# PM_Controller_v1p06.net
KiCad netlist of a schematic drawn in EAGLE
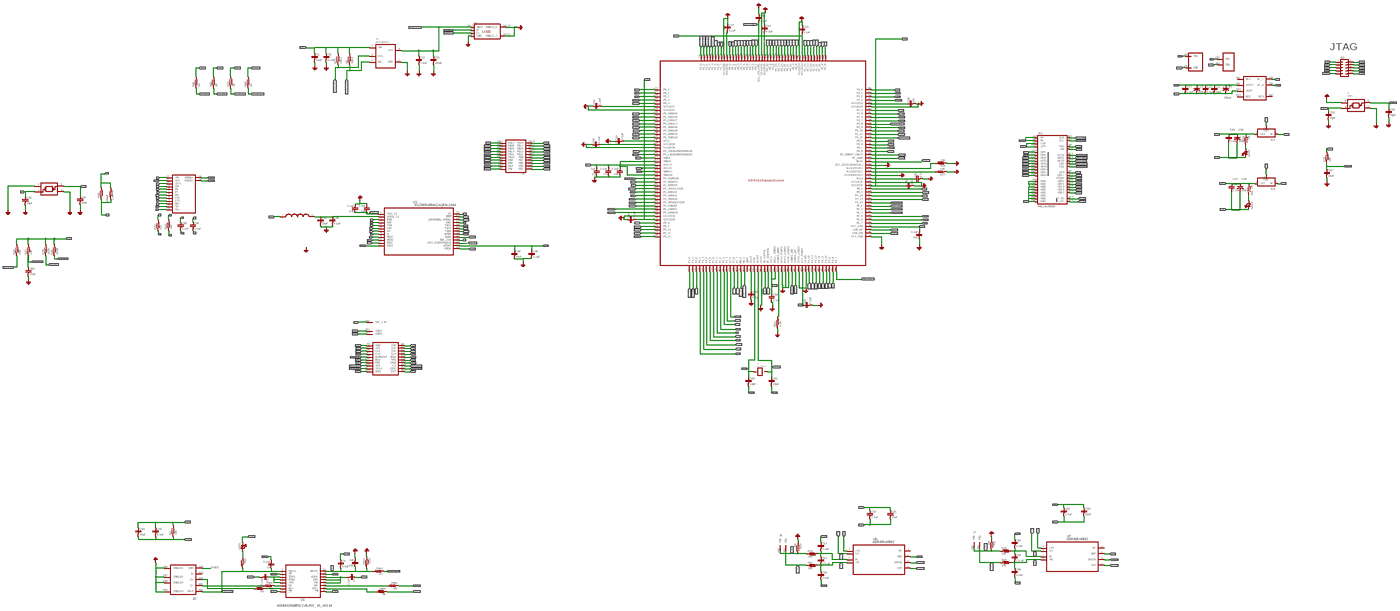
[diagram p0: schematic, sheet 1, overview]
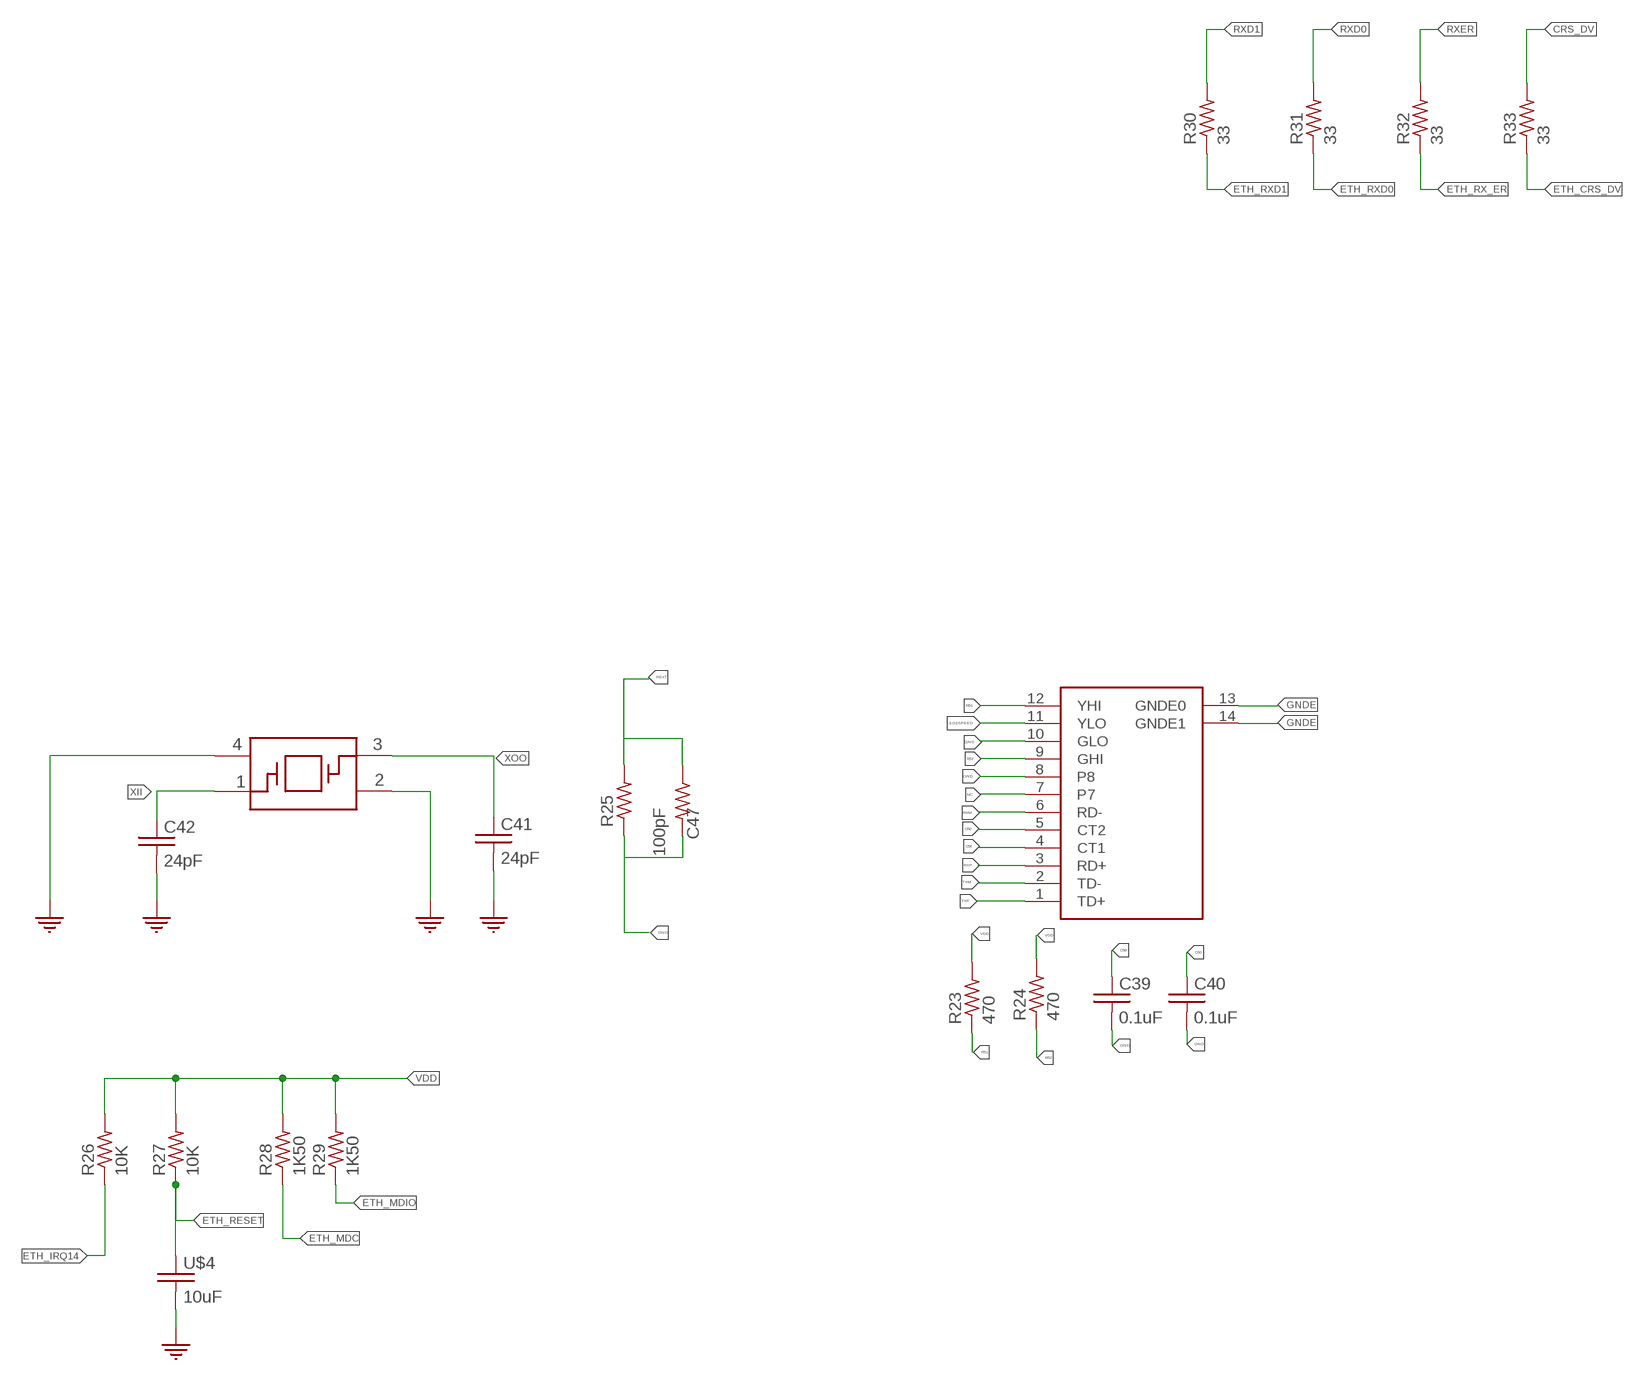
[diagram p1: schematic, sheet 1, part 1 of 7]
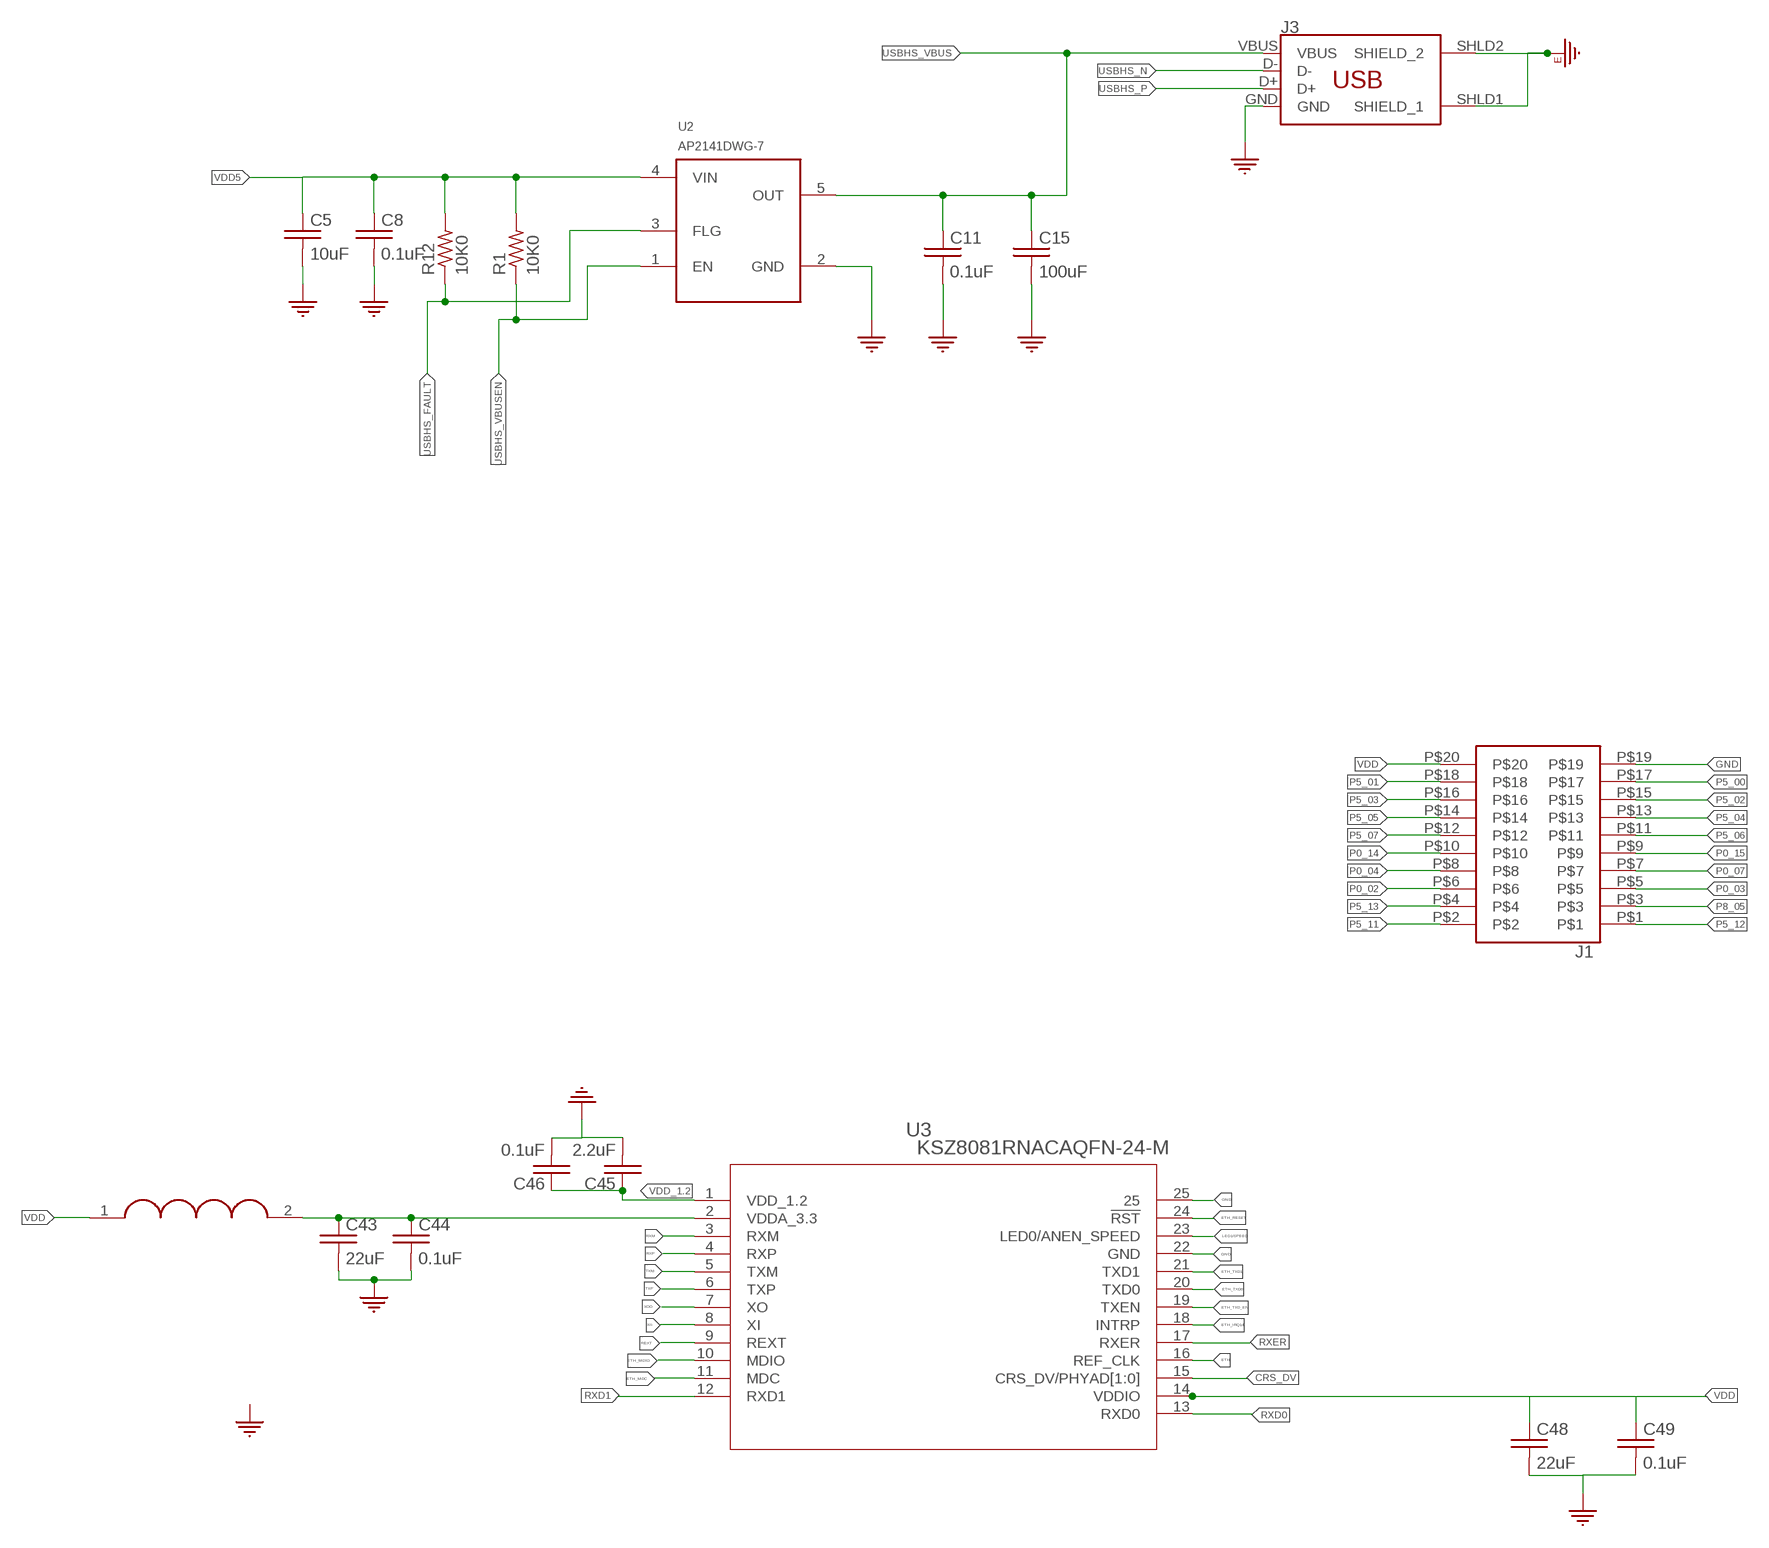
[diagram p2: schematic, sheet 1, part 2 of 7]
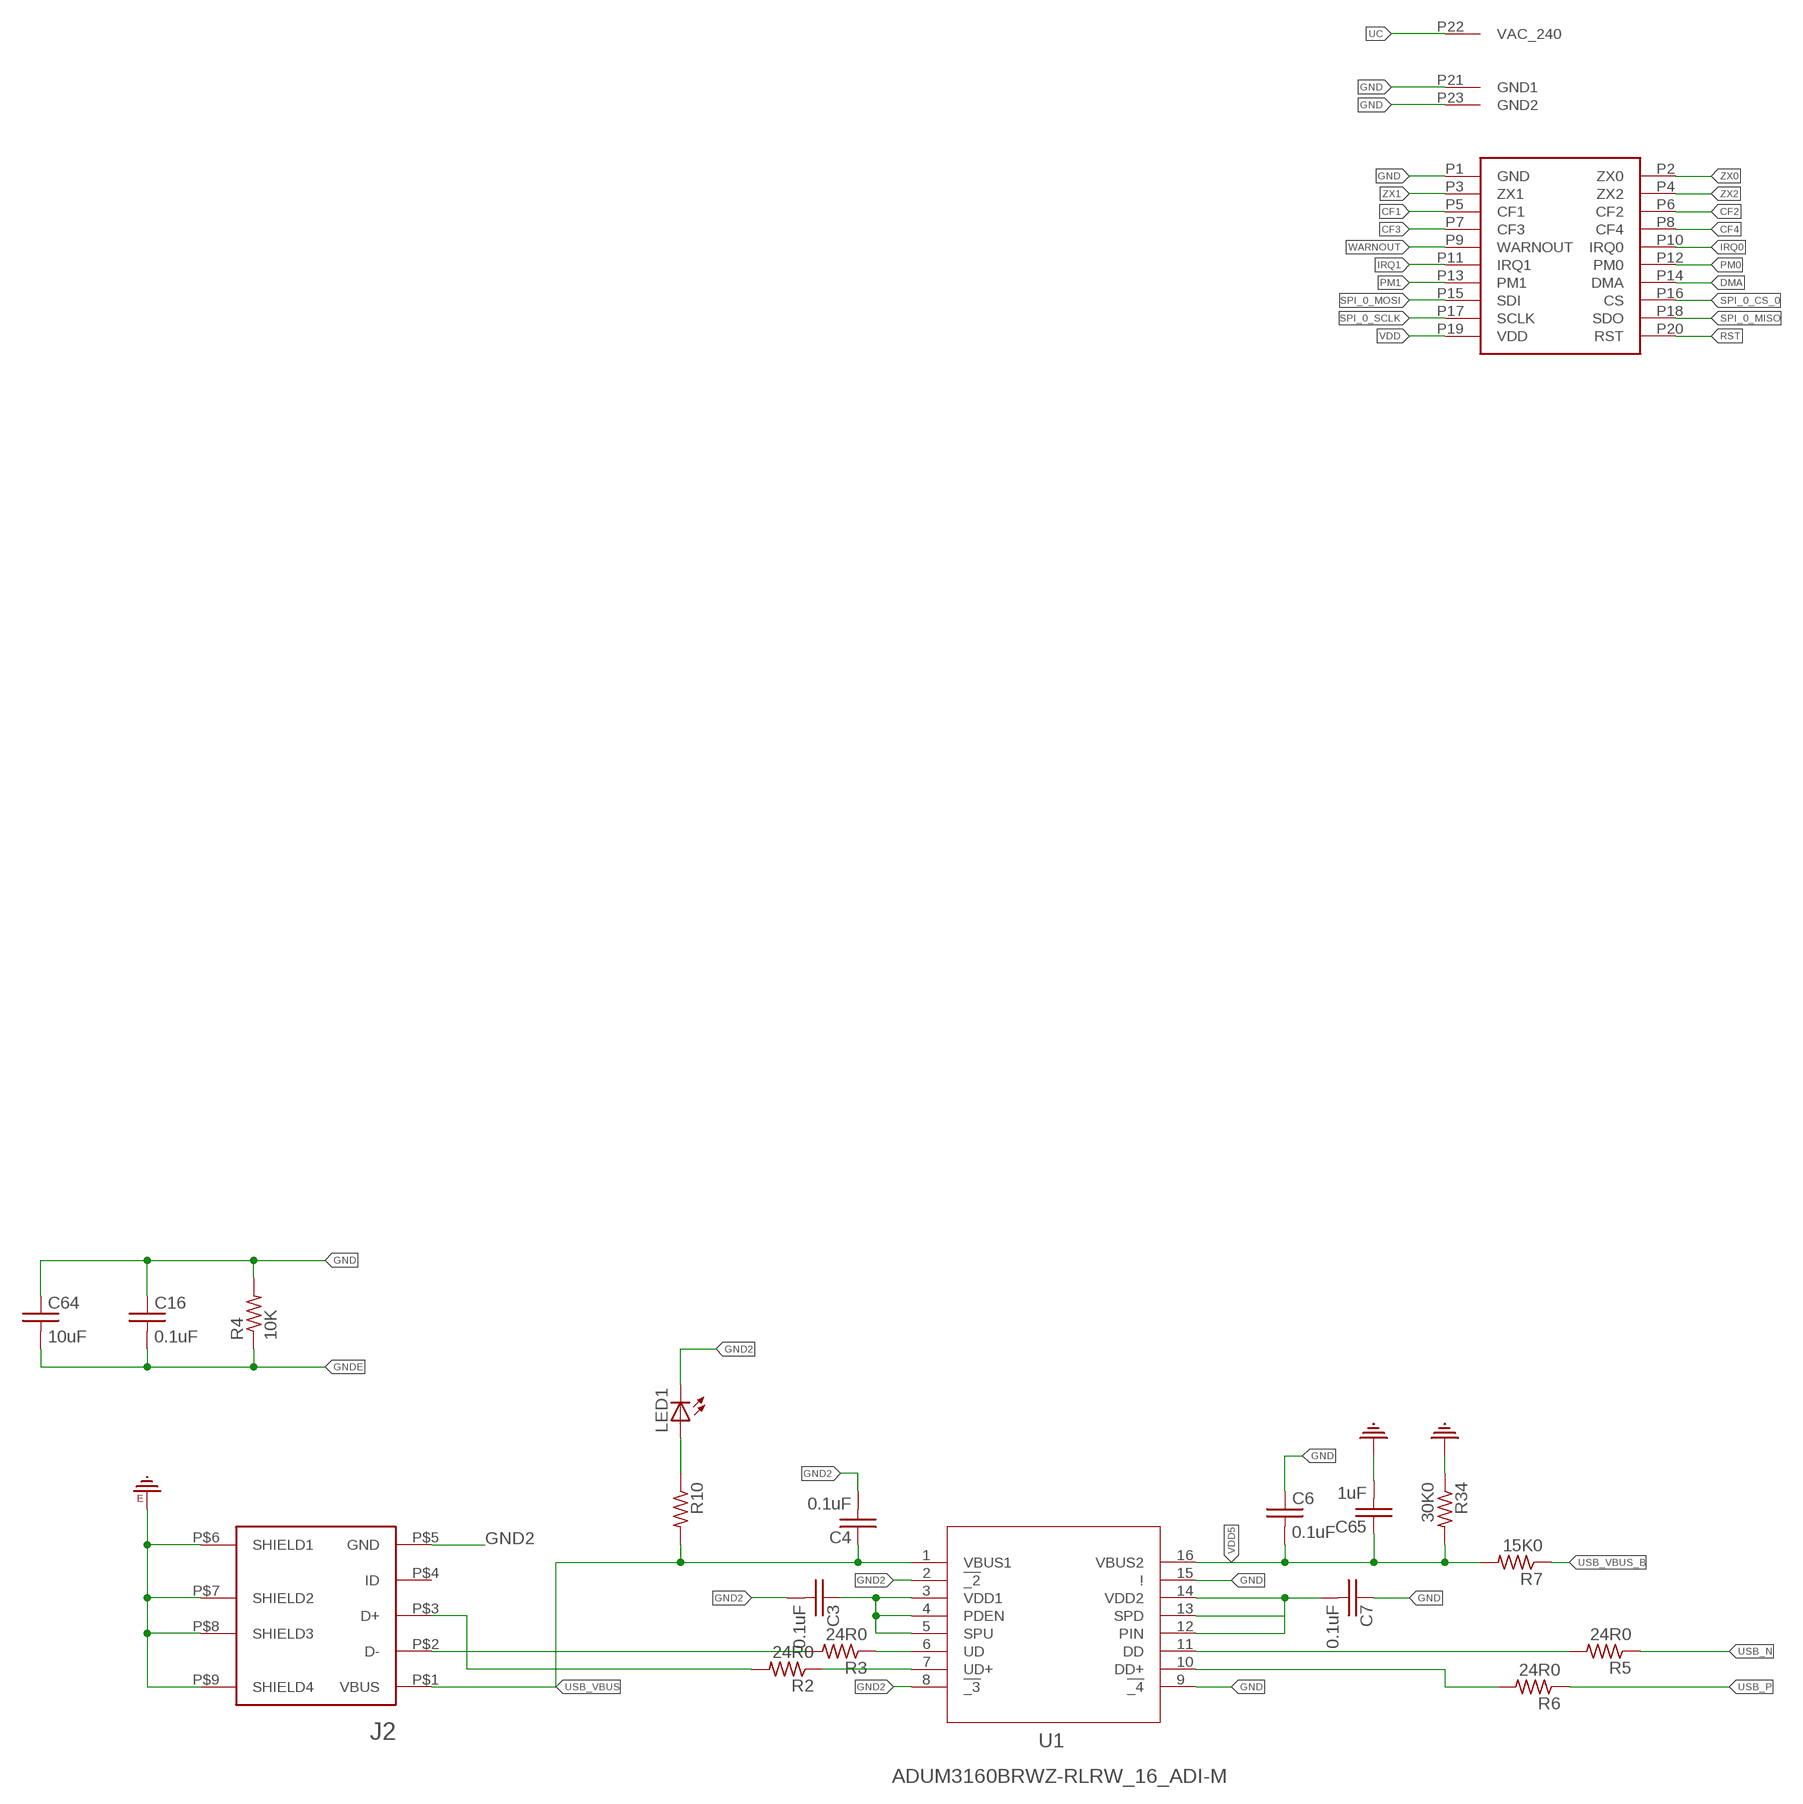
[diagram p3: schematic, sheet 1, part 3 of 7]
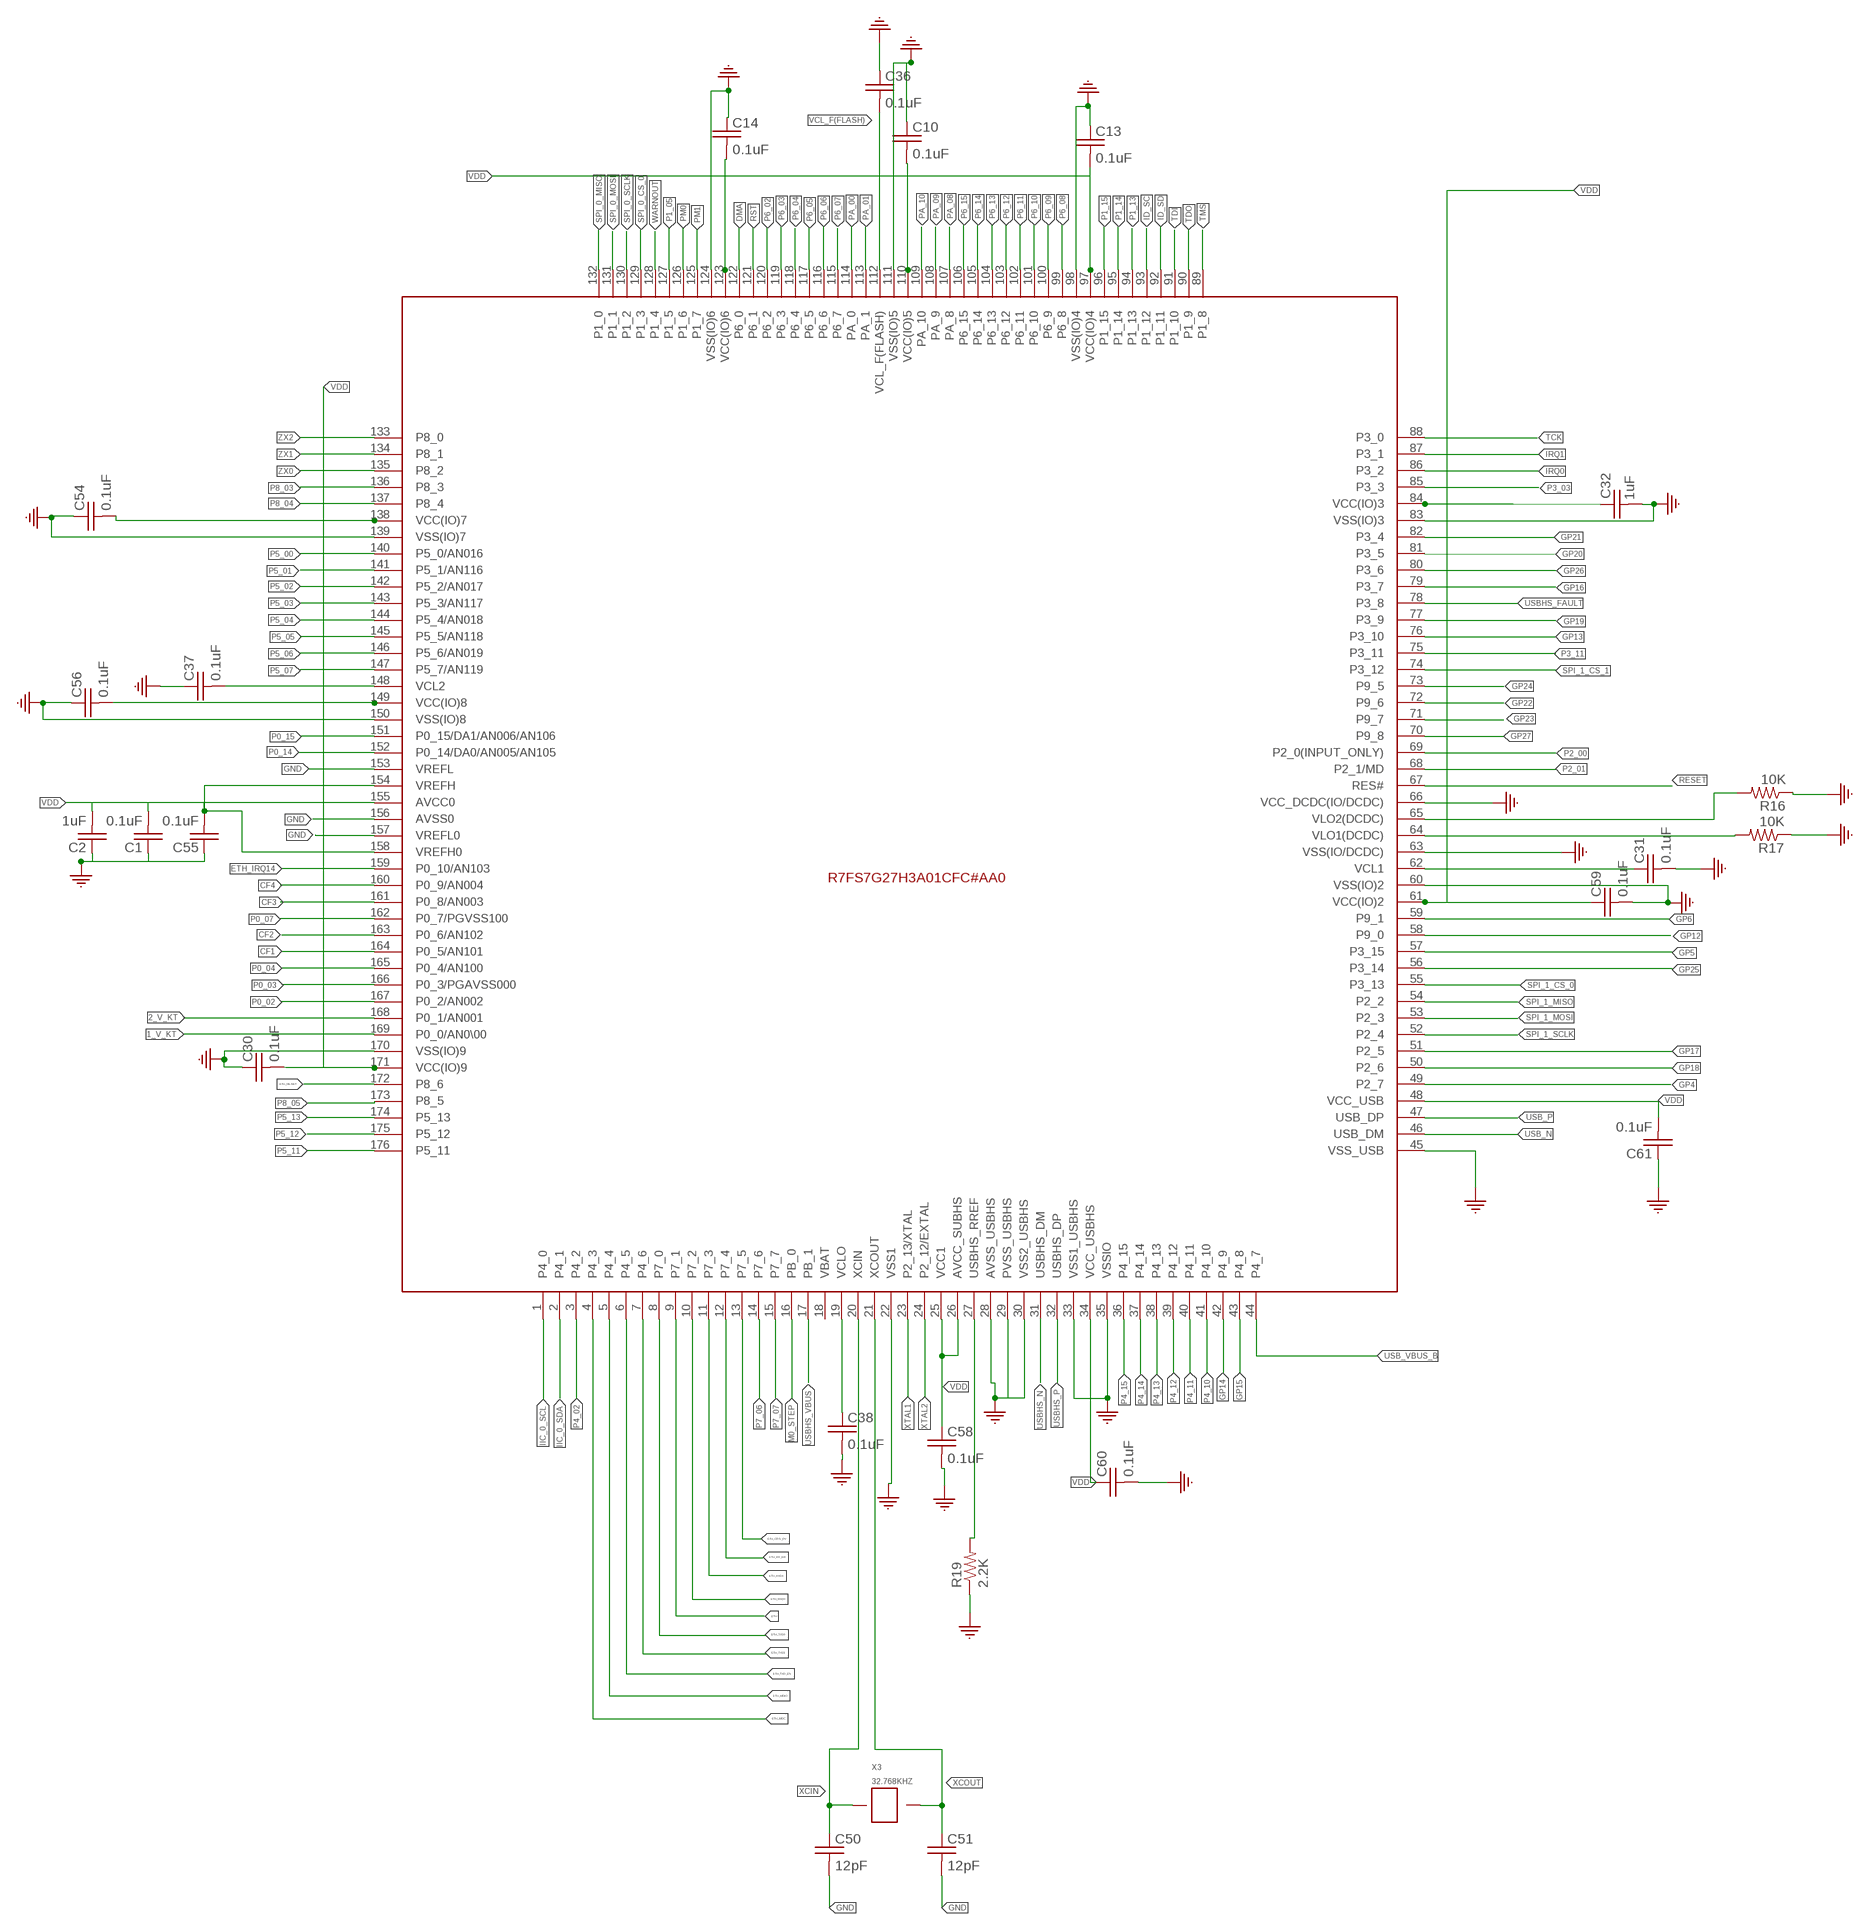
[diagram p4: schematic, sheet 1, part 4 of 7]
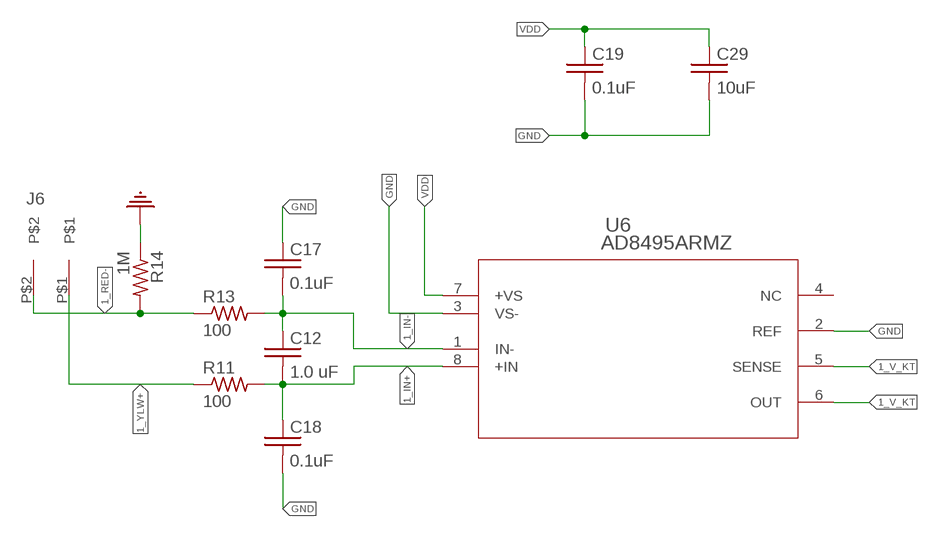
[diagram p5: schematic, sheet 1, part 5 of 7]
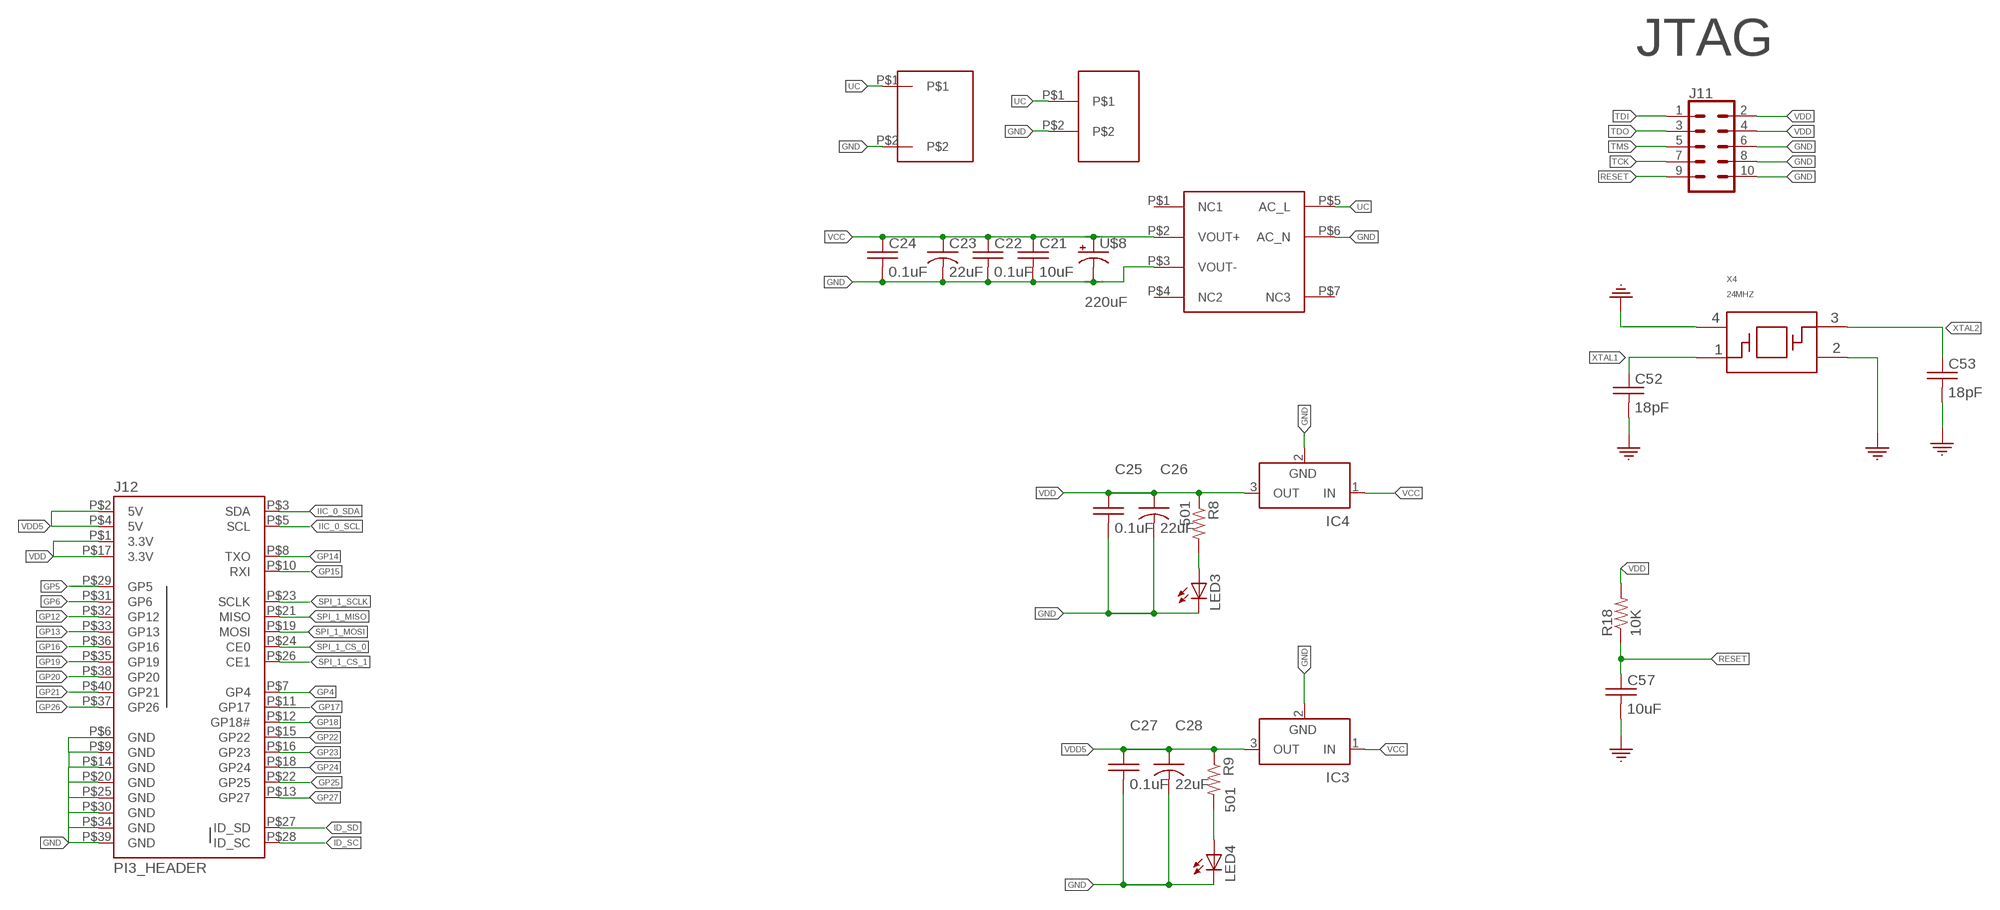
[diagram p6: schematic, sheet 1, part 6 of 7]
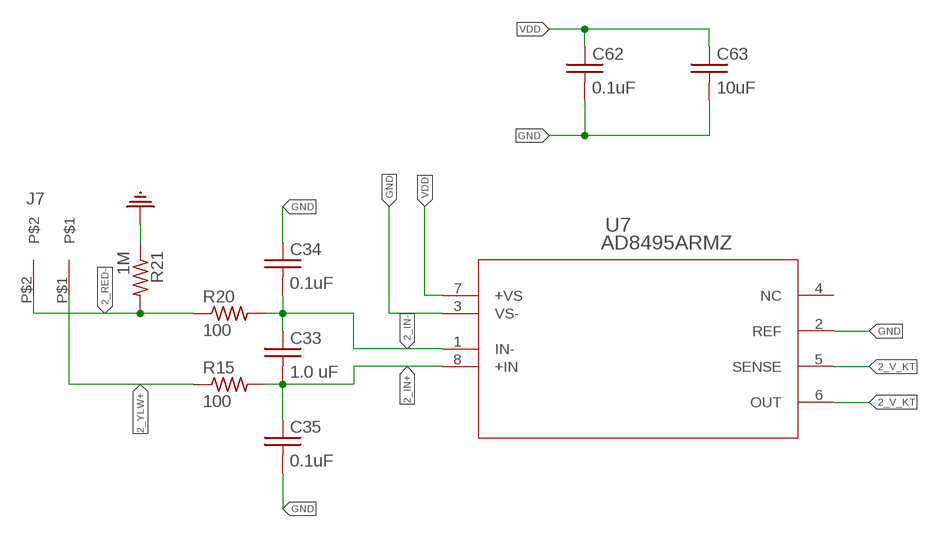
[diagram p7: schematic, sheet 1, part 7 of 7]

(export (version "E")
  (design (tool "Eeschema 10.0.6"))
  (components
    (comp (ref "C1")
      (value "0.1uF")
      (footprint "eagle-import:0402")
      (libsource (lib "eagle-import") (part "C_0402"))
    )
    (comp (ref "C2")
      (value "1uF")
      (footprint "eagle-import:0402")
      (libsource (lib "eagle-import") (part "C_0402"))
    )
    (comp (ref "C3")
      (value "0.1uF")
      (footprint "eagle-import:0402")
      (libsource (lib "eagle-import") (part "C_0402"))
    )
    (comp (ref "C4")
      (value "0.1uF")
      (footprint "eagle-import:0402")
      (libsource (lib "eagle-import") (part "C_0402"))
    )
    (comp (ref "C5")
      (value "10uF")
      (footprint "eagle-import:0402")
      (libsource (lib "eagle-import") (part "C_0402"))
    )
    (comp (ref "C6")
      (value "0.1uF")
      (footprint "eagle-import:0402")
      (libsource (lib "eagle-import") (part "C_0402"))
    )
    (comp (ref "C7")
      (value "0.1uF")
      (footprint "eagle-import:0402")
      (libsource (lib "eagle-import") (part "C_0402"))
    )
    (comp (ref "C8")
      (value "0.1uF")
      (footprint "eagle-import:0402")
      (libsource (lib "eagle-import") (part "C_0402"))
    )
    (comp (ref "C10")
      (value "0.1uF")
      (footprint "eagle-import:0402")
      (libsource (lib "eagle-import") (part "C_0402"))
    )
    (comp (ref "C11")
      (value "0.1uF")
      (footprint "eagle-import:0402")
      (libsource (lib "eagle-import") (part "C_0402"))
    )
    (comp (ref "C12")
      (value "1.0 uF")
      (footprint "eagle-import:0402")
      (libsource (lib "eagle-import") (part "C_0402"))
    )
    (comp (ref "C13")
      (value "0.1uF")
      (footprint "eagle-import:0402")
      (libsource (lib "eagle-import") (part "C_0402"))
    )
    (comp (ref "C14")
      (value "0.1uF")
      (footprint "eagle-import:0402")
      (libsource (lib "eagle-import") (part "C_0402"))
    )
    (comp (ref "C15")
      (value "100uF")
      (footprint "eagle-import:C1210")
      (libsource (lib "eagle-import") (part "C_1210"))
    )
    (comp (ref "C16")
      (value "0.1uF")
      (footprint "eagle-import:0402")
      (libsource (lib "eagle-import") (part "C_0402"))
    )
    (comp (ref "C17")
      (value "0.1uF")
      (footprint "eagle-import:0402")
      (libsource (lib "eagle-import") (part "C_0402"))
    )
    (comp (ref "C18")
      (value "0.1uF")
      (footprint "eagle-import:0402")
      (libsource (lib "eagle-import") (part "C_0402"))
    )
    (comp (ref "C19")
      (value "0.1uF")
      (footprint "eagle-import:0402")
      (libsource (lib "eagle-import") (part "C_0402"))
    )
    (comp (ref "C20")
      (value "CAP_THIN_FILM_TDK_32922CAP")
      (footprint "eagle-import:CAP_THIN_FILM_32922")
      (libsource (lib "eagle-import") (part "CAP_THIN_FILM_TDK_32922CAP"))
    )
    (comp (ref "C21")
      (value "10uF")
      (footprint "eagle-import:0402")
      (libsource (lib "eagle-import") (part "C_0402"))
    )
    (comp (ref "C22")
      (value "0.1uF")
      (footprint "eagle-import:0402")
      (libsource (lib "eagle-import") (part "C_0402"))
    )
    (comp (ref "C23")
      (value "22uF")
      (footprint "eagle-import:C1206")
      (libsource (lib "eagle-import") (part "C-USC1206"))
    )
    (comp (ref "C24")
      (value "0.1uF")
      (footprint "eagle-import:0402")
      (libsource (lib "eagle-import") (part "C_0402"))
    )
    (comp (ref "C25")
      (value "0.1uF")
      (footprint "eagle-import:0402")
      (libsource (lib "eagle-import") (part "C_0402"))
    )
    (comp (ref "C26")
      (value "22uF")
      (footprint "eagle-import:C1206")
      (libsource (lib "eagle-import") (part "C-USC1206"))
    )
    (comp (ref "C27")
      (value "0.1uF")
      (footprint "eagle-import:0402")
      (libsource (lib "eagle-import") (part "C_0402"))
    )
    (comp (ref "C28")
      (value "22uF")
      (footprint "eagle-import:C1206")
      (libsource (lib "eagle-import") (part "C-USC1206"))
    )
    (comp (ref "C29")
      (value "10uF")
      (footprint "eagle-import:0402")
      (libsource (lib "eagle-import") (part "C_0402"))
    )
    (comp (ref "C30")
      (value "0.1uF")
      (footprint "eagle-import:0402")
      (libsource (lib "eagle-import") (part "C_0402"))
    )
    (comp (ref "C31")
      (value "0.1uF")
      (footprint "eagle-import:0402")
      (libsource (lib "eagle-import") (part "C_0402"))
    )
    (comp (ref "C32")
      (value "1uF")
      (footprint "eagle-import:0402")
      (libsource (lib "eagle-import") (part "C_0402"))
    )
    (comp (ref "C33")
      (value "1.0 uF")
      (footprint "eagle-import:0402")
      (libsource (lib "eagle-import") (part "C_0402"))
    )
    (comp (ref "C34")
      (value "0.1uF")
      (footprint "eagle-import:0402")
      (libsource (lib "eagle-import") (part "C_0402"))
    )
    (comp (ref "C35")
      (value "0.1uF")
      (footprint "eagle-import:0402")
      (libsource (lib "eagle-import") (part "C_0402"))
    )
    (comp (ref "C36")
      (value "0.1uF")
      (footprint "eagle-import:0402")
      (libsource (lib "eagle-import") (part "C_0402"))
    )
    (comp (ref "C37")
      (value "0.1uF")
      (footprint "eagle-import:0402")
      (libsource (lib "eagle-import") (part "C_0402"))
    )
    (comp (ref "C38")
      (value "0.1uF")
      (footprint "eagle-import:0402")
      (libsource (lib "eagle-import") (part "C_0402"))
    )
    (comp (ref "C39")
      (value "0.1uF")
      (footprint "eagle-import:0402")
      (libsource (lib "eagle-import") (part "C_0402"))
    )
    (comp (ref "C40")
      (value "0.1uF")
      (footprint "eagle-import:0402")
      (libsource (lib "eagle-import") (part "C_0402"))
    )
    (comp (ref "C41")
      (value "24pF")
      (footprint "eagle-import:0402")
      (libsource (lib "eagle-import") (part "C_0402"))
    )
    (comp (ref "C42")
      (value "24pF")
      (footprint "eagle-import:0402")
      (libsource (lib "eagle-import") (part "C_0402"))
    )
    (comp (ref "C43")
      (value "22uF")
      (footprint "eagle-import:0603")
      (libsource (lib "eagle-import") (part "C_0603"))
    )
    (comp (ref "C44")
      (value "0.1uF")
      (footprint "eagle-import:0402")
      (libsource (lib "eagle-import") (part "C_0402"))
    )
    (comp (ref "C45")
      (value "2.2uF")
      (footprint "eagle-import:0402")
      (libsource (lib "eagle-import") (part "C_0402"))
    )
    (comp (ref "C46")
      (value "0.1uF")
      (footprint "eagle-import:0402")
      (libsource (lib "eagle-import") (part "C_0402"))
    )
    (comp (ref "C47")
      (value "100pF")
      (footprint "eagle-import:0402")
      (libsource (lib "eagle-import") (part "R_0402"))
    )
    (comp (ref "C48")
      (value "22uF")
      (footprint "eagle-import:0603")
      (libsource (lib "eagle-import") (part "C_0603"))
    )
    (comp (ref "C49")
      (value "0.1uF")
      (footprint "eagle-import:0402")
      (libsource (lib "eagle-import") (part "C_0402"))
    )
    (comp (ref "C50")
      (value "12pF")
      (footprint "eagle-import:0402")
      (libsource (lib "eagle-import") (part "C_0402"))
    )
    (comp (ref "C51")
      (value "12pF")
      (footprint "eagle-import:0402")
      (libsource (lib "eagle-import") (part "C_0402"))
    )
    (comp (ref "C52")
      (value "18pF")
      (footprint "eagle-import:0402")
      (libsource (lib "eagle-import") (part "C_0402"))
    )
    (comp (ref "C53")
      (value "18pF")
      (footprint "eagle-import:0402")
      (libsource (lib "eagle-import") (part "C_0402"))
    )
    (comp (ref "C54")
      (value "0.1uF")
      (footprint "eagle-import:0402")
      (libsource (lib "eagle-import") (part "C_0402"))
    )
    (comp (ref "C55")
      (value "0.1uF")
      (footprint "eagle-import:0402")
      (libsource (lib "eagle-import") (part "C_0402"))
    )
    (comp (ref "C56")
      (value "0.1uF")
      (footprint "eagle-import:0402")
      (libsource (lib "eagle-import") (part "C_0402"))
    )
    (comp (ref "C57")
      (value "10uF")
      (footprint "eagle-import:0402")
      (libsource (lib "eagle-import") (part "C_0402"))
    )
    (comp (ref "C58")
      (value "0.1uF")
      (footprint "eagle-import:0402")
      (libsource (lib "eagle-import") (part "C_0402"))
    )
    (comp (ref "C59")
      (value "0.1uF")
      (footprint "eagle-import:0402")
      (libsource (lib "eagle-import") (part "C_0402"))
    )
    (comp (ref "C60")
      (value "0.1uF")
      (footprint "eagle-import:0402")
      (libsource (lib "eagle-import") (part "C_0402"))
    )
    (comp (ref "C61")
      (value "0.1uF")
      (footprint "eagle-import:0402")
      (libsource (lib "eagle-import") (part "C_0402"))
    )
    (comp (ref "C62")
      (value "0.1uF")
      (footprint "eagle-import:0402")
      (libsource (lib "eagle-import") (part "C_0402"))
    )
    (comp (ref "C63")
      (value "10uF")
      (footprint "eagle-import:0402")
      (libsource (lib "eagle-import") (part "C_0402"))
    )
    (comp (ref "C64")
      (value "10uF")
      (footprint "eagle-import:0402")
      (libsource (lib "eagle-import") (part "C_0402"))
    )
    (comp (ref "C65")
      (value "1uF")
      (footprint "eagle-import:0402")
      (libsource (lib "eagle-import") (part "C_0402"))
    )
    (comp (ref "FB2/2")
      (value "FB_0805_120_OHM")
      (footprint "eagle-import:0805")
      (libsource (lib "eagle-import") (part "FB_0805_120_OHM"))
    )
    (comp (ref "IC3")
      (value "LT1129CST5")
      (footprint "eagle-import:SOT223")
      (fields (field (name "MPN") "LT1129CST-5#PBF"))
      (libsource (lib "eagle-import") (part "LT1129CST5"))
    )
    (comp (ref "IC4")
      (value "LT1129CST3")
      (footprint "eagle-import:SOT223")
      (fields (field (name "MPN") "LT1129CST-5#PBF"))
      (libsource (lib "eagle-import") (part "LT1129CST3"))
    )
    (comp (ref "J1")
      (value "2_X_10_HEADER_GENERIC")
      (footprint "eagle-import:2_X_10_.1_INCH")
      (libsource (lib "eagle-import") (part "2_X_10_HEADER_GENERIC"))
    )
    (comp (ref "J2")
      (value "USB_MICRO-B")
      (footprint "eagle-import:USB_MICRO-B")
      (libsource (lib "eagle-import") (part "USB_MICRO-B"))
    )
    (comp (ref "J3")
      (value "USB_A")
      (footprint "eagle-import:USB_A_SMT")
      (libsource (lib "eagle-import") (part "USB_A"))
    )
    (comp (ref "J4")
      (value "RJ45_WITH_ELEC")
      (footprint "eagle-import:RJ45_TH_ELEC")
      (libsource (lib "eagle-import") (part "RJ45_WITH_ELEC"))
    )
    (comp (ref "J6")
      (value "3.81MM_1_X_2_RT_ANGLE_PLUG_HEADER")
      (footprint "eagle-import:2_3.81MM_PITCH")
      (libsource (lib "eagle-import") (part "3.81MM_1_X_2_RT_ANGLE_PLUG_HEADER"))
    )
    (comp (ref "J7")
      (value "3.81MM_1_X_2_RT_ANGLE_PLUG_HEADER")
      (footprint "eagle-import:2_3.81MM_PITCH")
      (libsource (lib "eagle-import") (part "3.81MM_1_X_2_RT_ANGLE_PLUG_HEADER"))
    )
    (comp (ref "J11")
      (value "CONN_05X2PTH")
      (footprint "eagle-import:2X5")
      (libsource (lib "eagle-import") (part "CONN_05X2PTH"))
    )
    (comp (ref "J12")
      (value "PI3_HEADER")
      (footprint "eagle-import:HEADER_2_X_20_.1_INCH")
      (libsource (lib "eagle-import") (part "PI3_HEADER"))
    )
    (comp (ref "LED1")
      (value "LED_0805_GREEN")
      (footprint "eagle-import:LED_0805_GREEN")
      (libsource (lib "eagle-import") (part "LED_0805_GREEN"))
    )
    (comp (ref "LED3")
      (value "LED_0805_GREEN")
      (footprint "eagle-import:LED_0805_GREEN")
      (libsource (lib "eagle-import") (part "LED_0805_GREEN"))
    )
    (comp (ref "LED4")
      (value "LED_0805_GREEN")
      (footprint "eagle-import:LED_0805_GREEN")
      (libsource (lib "eagle-import") (part "LED_0805_GREEN"))
    )
    (comp (ref "R1")
      (value "10K0")
      (footprint "eagle-import:0402")
      (libsource (lib "eagle-import") (part "R_0402"))
    )
    (comp (ref "R2")
      (value "24R0")
      (footprint "eagle-import:0402")
      (libsource (lib "eagle-import") (part "R_0402"))
    )
    (comp (ref "R3")
      (value "24R0")
      (footprint "eagle-import:0402")
      (libsource (lib "eagle-import") (part "R_0402"))
    )
    (comp (ref "R4")
      (value "10K")
      (footprint "eagle-import:0402")
      (libsource (lib "eagle-import") (part "R_0402"))
    )
    (comp (ref "R5")
      (value "24R0")
      (footprint "eagle-import:0402")
      (libsource (lib "eagle-import") (part "R_0402"))
    )
    (comp (ref "R6")
      (value "24R0")
      (footprint "eagle-import:0402")
      (libsource (lib "eagle-import") (part "R_0402"))
    )
    (comp (ref "R7")
      (value "15K0")
      (footprint "eagle-import:0402")
      (libsource (lib "eagle-import") (part "R_0402"))
    )
    (comp (ref "R8")
      (value "501")
      (footprint "eagle-import:0402")
      (libsource (lib "eagle-import") (part "R_0402"))
    )
    (comp (ref "R9")
      (value "501")
      (footprint "eagle-import:0402")
      (libsource (lib "eagle-import") (part "R_0402"))
    )
    (comp (ref "R10")
      (value "R_0402")
      (footprint "eagle-import:0402")
      (libsource (lib "eagle-import") (part "R_0402"))
    )
    (comp (ref "R11")
      (value "100")
      (footprint "eagle-import:0402")
      (libsource (lib "eagle-import") (part "R_0402"))
    )
    (comp (ref "R12")
      (value "10K0")
      (footprint "eagle-import:0402")
      (libsource (lib "eagle-import") (part "R_0402"))
    )
    (comp (ref "R13")
      (value "100")
      (footprint "eagle-import:0402")
      (libsource (lib "eagle-import") (part "R_0402"))
    )
    (comp (ref "R14")
      (value "1M")
      (footprint "eagle-import:0402")
      (libsource (lib "eagle-import") (part "R_0402"))
    )
    (comp (ref "R15")
      (value "100")
      (footprint "eagle-import:0402")
      (libsource (lib "eagle-import") (part "R_0402"))
    )
    (comp (ref "R16")
      (value "10K")
      (footprint "eagle-import:0402")
      (libsource (lib "eagle-import") (part "R_0402"))
    )
    (comp (ref "R17")
      (value "10K")
      (footprint "eagle-import:0402")
      (libsource (lib "eagle-import") (part "R_0402"))
    )
    (comp (ref "R18")
      (value "10K")
      (footprint "eagle-import:0402")
      (libsource (lib "eagle-import") (part "R_0402"))
    )
    (comp (ref "R19")
      (value "2.2K")
      (footprint "eagle-import:0402")
      (libsource (lib "eagle-import") (part "R_0402"))
    )
    (comp (ref "R20")
      (value "100")
      (footprint "eagle-import:0402")
      (libsource (lib "eagle-import") (part "R_0402"))
    )
    (comp (ref "R21")
      (value "1M")
      (footprint "eagle-import:0402")
      (libsource (lib "eagle-import") (part "R_0402"))
    )
    (comp (ref "R23")
      (value "470")
      (footprint "eagle-import:0402")
      (libsource (lib "eagle-import") (part "R_0402"))
    )
    (comp (ref "R24")
      (value "470")
      (footprint "eagle-import:0402")
      (libsource (lib "eagle-import") (part "R_0402"))
    )
    (comp (ref "R25")
      (value "6k49")
      (footprint "eagle-import:0402")
      (libsource (lib "eagle-import") (part "R_0402"))
    )
    (comp (ref "R26")
      (value "10K")
      (footprint "eagle-import:0402")
      (libsource (lib "eagle-import") (part "R_0402"))
    )
    (comp (ref "R27")
      (value "10K")
      (footprint "eagle-import:0402")
      (libsource (lib "eagle-import") (part "R_0402"))
    )
    (comp (ref "R28")
      (value "1K50")
      (footprint "eagle-import:0402")
      (libsource (lib "eagle-import") (part "R_0402"))
    )
    (comp (ref "R29")
      (value "1K50")
      (footprint "eagle-import:0402")
      (libsource (lib "eagle-import") (part "R_0402"))
    )
    (comp (ref "R30")
      (value "33")
      (footprint "eagle-import:0402")
      (libsource (lib "eagle-import") (part "R_0402"))
    )
    (comp (ref "R31")
      (value "33")
      (footprint "eagle-import:0402")
      (libsource (lib "eagle-import") (part "R_0402"))
    )
    (comp (ref "R32")
      (value "33")
      (footprint "eagle-import:0402")
      (libsource (lib "eagle-import") (part "R_0402"))
    )
    (comp (ref "R33")
      (value "33")
      (footprint "eagle-import:0402")
      (libsource (lib "eagle-import") (part "R_0402"))
    )
    (comp (ref "R34")
      (value "30K0")
      (footprint "eagle-import:0402")
      (libsource (lib "eagle-import") (part "R_0402"))
    )
    (comp (ref "U$2")
      (value "METER_BASE")
      (footprint "eagle-import:METER_BASE")
      (libsource (lib "eagle-import") (part "METER_BASE"))
    )
    (comp (ref "U$3")
      (value "XTAL_25_MHZ")
      (footprint "eagle-import:SMD_3225")
      (libsource (lib "eagle-import") (part "XTAL_25_MHZ"))
    )
    (comp (ref "U$4")
      (value "10uF")
      (footprint "eagle-import:0402")
      (libsource (lib "eagle-import") (part "C_0402"))
    )
    (comp (ref "U$7")
      (value "VAR_10MM_VDRUS10")
      (footprint "eagle-import:VAR_10MM_VDRUS10")
      (libsource (lib "eagle-import") (part "VAR_10MM_VDRUS10"))
    )
    (comp (ref "U$8")
      (value "220uF")
      (footprint "eagle-import:C_AL_ELECTROLYTIC_SMD_220UF")
      (libsource (lib "eagle-import") (part "C_AL_ELECTROLYTIC_SMD_220UF"))
    )
    (comp (ref "U1")
      (value "ADUM3160BRWZ-RLRW_16_ADI-M")
      (footprint "eagle-import:RW_16_ADI-M")
      (fields
        (field (name "MANUFACTURER_PART_NUMBER") "ADUM3160BRWZ-RL")
        (field (name "COPYRIGHT") "Copyright (C) 2018 Accelerated Designs. All rights reserved")
      )
      (libsource (lib "eagle-import") (part "ADUM3160BRWZ-RLRW_16_ADI-M"))
    )
    (comp (ref "U2")
      (value "AP2141DWG-5")
      (footprint "eagle-import:SOT-23-5")
      (libsource (lib "eagle-import") (part "AP2141DWG-5"))
    )
    (comp (ref "U3")
      (value "KSZ8081RNACAQFN-24-M")
      (footprint "eagle-import:QFN-24-M")
      (fields (field (name "MANUFACTURER_PART_NUMBER") "KSZ8081RNACA"))
      (libsource (lib "eagle-import") (part "KSZ8081RNACAQFN-24-M"))
    )
    (comp (ref "U4")
      (value "S7G2LQFP176")
      (footprint "eagle-import:LQFP176_24X24")
      (fields (field (name "PARTNO") "R7FS7G27H3A01CFC#AA0"))
      (libsource (lib "eagle-import") (part "RENESAS_S7G2_X_176"))
    )
    (comp (ref "U5")
      (value "TMLM_04109")
      (footprint "eagle-import:TMLM04")
      (libsource (lib "eagle-import") (part "TMLM_04109"))
    )
    (comp (ref "U6")
      (value "AD8495ARMZ")
      (footprint "eagle-import:RM_8_ADI")
      (libsource (lib "eagle-import") (part "AD8495ARMZ"))
    )
    (comp (ref "U7")
      (value "AD8495ARMZ")
      (footprint "eagle-import:RM_8_ADI")
      (libsource (lib "eagle-import") (part "AD8495ARMZ"))
    )
    (comp (ref "X3")
      (value "32.768KHZ")
      (footprint "eagle-import:SMD_X_2_PADS")
      (libsource (lib "eagle-import") (part "XTAL_32.768KHZ"))
    )
    (comp (ref "X4")
      (value "24MHZ")
      (footprint "eagle-import:SMD_3225")
      (libsource (lib "eagle-import") (part "XTAL_24_MHZ"))
    )
  )
  (nets
    (net (code "1") (name "1_IN+") (class "Default")
      (node (ref "C12") (pin "P$2") (pinfunction "2_P$2") (pintype "passive"))
      (node (ref "C18") (pin "P$1") (pinfunction "1_P$1") (pintype "passive"))
      (node (ref "R11") (pin "P$2") (pinfunction "2_P$2") (pintype "passive"))
      (node (ref "U6") (pin "8") (pinfunction "+IN_8") (pintype "input"))
    )
    (net (code "2") (name "1_IN-") (class "Default")
      (node (ref "C12") (pin "P$1") (pinfunction "1_P$1") (pintype "passive"))
      (node (ref "C17") (pin "P$2") (pinfunction "2_P$2") (pintype "passive"))
      (node (ref "R13") (pin "P$2") (pinfunction "2_P$2") (pintype "passive"))
      (node (ref "U6") (pin "1") (pinfunction "IN-_1") (pintype "input"))
    )
    (net (code "3") (name "1_RED-") (class "Default")
      (node (ref "J6") (pin "P$2") (pinfunction "P$2_P$2") (pintype "bidirectional"))
      (node (ref "R13") (pin "P$1") (pinfunction "1_P$1") (pintype "passive"))
      (node (ref "R14") (pin "P$2") (pinfunction "2_P$2") (pintype "passive"))
    )
    (net (code "4") (name "1_V_KT") (class "Default")
      (node (ref "U4") (pin "169") (pinfunction "P0_0/AN0\\00_169") (pintype "bidirectional"))
      (node (ref "U6") (pin "5") (pinfunction "SENSE_5") (pintype "passive"))
      (node (ref "U6") (pin "6") (pinfunction "OUT_6") (pintype "output"))
    )
    (net (code "5") (name "1_YLW+") (class "Default")
      (node (ref "J6") (pin "P$1") (pinfunction "P$1_P$1") (pintype "bidirectional"))
      (node (ref "R11") (pin "P$1") (pinfunction "1_P$1") (pintype "passive"))
    )
    (net (code "6") (name "2_IN+") (class "Default")
      (node (ref "C33") (pin "P$2") (pinfunction "2_P$2") (pintype "passive"))
      (node (ref "C35") (pin "P$1") (pinfunction "1_P$1") (pintype "passive"))
      (node (ref "R15") (pin "P$2") (pinfunction "2_P$2") (pintype "passive"))
      (node (ref "U7") (pin "8") (pinfunction "+IN_8") (pintype "input"))
    )
    (net (code "7") (name "2_IN-") (class "Default")
      (node (ref "C33") (pin "P$1") (pinfunction "1_P$1") (pintype "passive"))
      (node (ref "C34") (pin "P$2") (pinfunction "2_P$2") (pintype "passive"))
      (node (ref "R20") (pin "P$2") (pinfunction "2_P$2") (pintype "passive"))
      (node (ref "U7") (pin "1") (pinfunction "IN-_1") (pintype "input"))
    )
    (net (code "8") (name "2_RED-") (class "Default")
      (node (ref "J7") (pin "P$2") (pinfunction "P$2_P$2") (pintype "bidirectional"))
      (node (ref "R20") (pin "P$1") (pinfunction "1_P$1") (pintype "passive"))
      (node (ref "R21") (pin "P$2") (pinfunction "2_P$2") (pintype "passive"))
    )
    (net (code "9") (name "2_V_KT") (class "Default")
      (node (ref "U4") (pin "168") (pinfunction "P0_1/AN001_168") (pintype "bidirectional"))
      (node (ref "U7") (pin "5") (pinfunction "SENSE_5") (pintype "passive"))
      (node (ref "U7") (pin "6") (pinfunction "OUT_6") (pintype "output"))
    )
    (net (code "10") (name "2_YLW+") (class "Default")
      (node (ref "J7") (pin "P$1") (pinfunction "P$1_P$1") (pintype "bidirectional"))
      (node (ref "R15") (pin "P$1") (pinfunction "1_P$1") (pintype "passive"))
    )
    (net (code "11") (name "C58") (class "Default")
      (node (ref "C39") (pin "P$1") (pinfunction "1_P$1") (pintype "passive"))
      (node (ref "J4") (pin "4") (pinfunction "CT1_4") (pintype "bidirectional"))
    )
    (net (code "12") (name "C60") (class "Default")
      (node (ref "C40") (pin "P$1") (pinfunction "1_P$1") (pintype "passive"))
      (node (ref "J4") (pin "5") (pinfunction "CT2_5") (pintype "bidirectional"))
    )
    (net (code "13") (name "CF1") (class "Default")
      (node (ref "U$2") (pin "P5") (pinfunction "CF1_P5") (pintype "bidirectional"))
      (node (ref "U4") (pin "164") (pinfunction "P0_5/AN101_164") (pintype "bidirectional"))
    )
    (net (code "14") (name "CF2") (class "Default")
      (node (ref "U$2") (pin "P6") (pinfunction "CF2_P6") (pintype "bidirectional"))
      (node (ref "U4") (pin "163") (pinfunction "P0_6/AN102_163") (pintype "bidirectional"))
    )
    (net (code "15") (name "CF3") (class "Default")
      (node (ref "U$2") (pin "P7") (pinfunction "CF3_P7") (pintype "bidirectional"))
      (node (ref "U4") (pin "161") (pinfunction "P0_8/AN003_161") (pintype "bidirectional"))
    )
    (net (code "16") (name "CF4") (class "Default")
      (node (ref "U$2") (pin "P8") (pinfunction "CF4_P8") (pintype "bidirectional"))
      (node (ref "U4") (pin "160") (pinfunction "P0_9/AN004_160") (pintype "bidirectional"))
    )
    (net (code "17") (name "CRS_DV") (class "Default")
      (node (ref "R33") (pin "P$2") (pinfunction "2_P$2") (pintype "passive"))
      (node (ref "U3") (pin "15") (pinfunction "CRS_DV/PHYAD[1:0]_15") (pintype "bidirectional"))
    )
    (net (code "18") (name "DMA") (class "Default")
      (node (ref "U$2") (pin "P14") (pinfunction "DMA_P14") (pintype "bidirectional"))
      (node (ref "U4") (pin "122") (pinfunction "P6_0_122") (pintype "bidirectional"))
    )
    (net (code "19") (name "ETH") (class "Default")
      (node (ref "U3") (pin "16") (pinfunction "REF_CLK_16") (pintype "bidirectional"))
      (node (ref "U4") (pin "9") (pinfunction "P7_1_9") (pintype "bidirectional"))
    )
    (net (code "20") (name "ETH_CRS_DV") (class "Default")
      (node (ref "R33") (pin "P$1") (pinfunction "1_P$1") (pintype "passive"))
      (node (ref "U4") (pin "13") (pinfunction "P7_5_13") (pintype "bidirectional"))
    )
    (net (code "21") (name "ETH_IRQ14") (class "Default")
      (node (ref "R26") (pin "P$1") (pinfunction "1_P$1") (pintype "passive"))
      (node (ref "U3") (pin "18") (pinfunction "INTRP_18") (pintype "bidirectional"))
      (node (ref "U4") (pin "159") (pinfunction "P0_10/AN103_159") (pintype "bidirectional"))
    )
    (net (code "22") (name "ETH_MDC") (class "Default")
      (node (ref "R28") (pin "P$1") (pinfunction "1_P$1") (pintype "passive"))
      (node (ref "U3") (pin "11") (pinfunction "MDC_11") (pintype "input"))
      (node (ref "U4") (pin "4") (pinfunction "P4_3_4") (pintype "bidirectional"))
    )
    (net (code "23") (name "ETH_MDIO") (class "Default")
      (node (ref "R29") (pin "P$1") (pinfunction "1_P$1") (pintype "passive"))
      (node (ref "U3") (pin "10") (pinfunction "MDIO_10") (pintype "bidirectional"))
      (node (ref "U4") (pin "5") (pinfunction "P4_4_5") (pintype "bidirectional"))
    )
    (net (code "24") (name "ETH_RESET") (class "Default")
      (node (ref "R27") (pin "P$1") (pinfunction "1_P$1") (pintype "passive"))
      (node (ref "U$4") (pin "P$1") (pinfunction "1_P$1") (pintype "passive"))
      (node (ref "U3") (pin "24") (pinfunction "~{RST}_24") (pintype "input"))
      (node (ref "U4") (pin "172") (pinfunction "P8_6_172") (pintype "bidirectional"))
    )
    (net (code "25") (name "ETH_RXD0") (class "Default")
      (node (ref "R31") (pin "P$1") (pinfunction "1_P$1") (pintype "passive"))
      (node (ref "U4") (pin "10") (pinfunction "P7_2_10") (pintype "bidirectional"))
    )
    (net (code "26") (name "ETH_RXD1") (class "Default")
      (node (ref "R30") (pin "P$1") (pinfunction "1_P$1") (pintype "passive"))
      (node (ref "U4") (pin "11") (pinfunction "P7_3_11") (pintype "bidirectional"))
    )
    (net (code "27") (name "ETH_RX_ER") (class "Default")
      (node (ref "R32") (pin "P$1") (pinfunction "1_P$1") (pintype "passive"))
      (node (ref "U4") (pin "12") (pinfunction "P7_4_12") (pintype "bidirectional"))
    )
    (net (code "28") (name "ETH_TXD0") (class "Default")
      (node (ref "U3") (pin "20") (pinfunction "TXD0_20") (pintype "input"))
      (node (ref "U4") (pin "8") (pinfunction "P7_0_8") (pintype "bidirectional"))
    )
    (net (code "29") (name "ETH_TXD1") (class "Default")
      (node (ref "U3") (pin "21") (pinfunction "TXD1_21") (pintype "bidirectional"))
      (node (ref "U4") (pin "7") (pinfunction "P4_6_7") (pintype "bidirectional"))
    )
    (net (code "30") (name "ETH_TXD_EN") (class "Default")
      (node (ref "U3") (pin "19") (pinfunction "TXEN_19") (pintype "input"))
      (node (ref "U4") (pin "6") (pinfunction "P4_5_6") (pintype "bidirectional"))
    )
    (net (code "31") (name "GND") (class "Default")
      (node (ref "C1") (pin "P$1") (pinfunction "1_P$1") (pintype "passive"))
      (node (ref "C10") (pin "P$1") (pinfunction "1_P$1") (pintype "passive"))
      (node (ref "C11") (pin "P$2") (pinfunction "2_P$2") (pintype "passive"))
      (node (ref "C13") (pin "P$1") (pinfunction "1_P$1") (pintype "passive"))
      (node (ref "C14") (pin "P$1") (pinfunction "1_P$1") (pintype "passive"))
      (node (ref "C15") (pin "2") (pinfunction "2_2") (pintype "passive"))
      (node (ref "C16") (pin "P$1") (pinfunction "1_P$1") (pintype "passive"))
      (node (ref "C17") (pin "P$1") (pinfunction "1_P$1") (pintype "passive"))
      (node (ref "C18") (pin "P$2") (pinfunction "2_P$2") (pintype "passive"))
      (node (ref "C19") (pin "P$2") (pinfunction "2_P$2") (pintype "passive"))
      (node (ref "C2") (pin "P$1") (pinfunction "1_P$1") (pintype "passive"))
      (node (ref "C20") (pin "P$2") (pinfunction "P$2_P$2") (pintype "bidirectional"))
      (node (ref "C21") (pin "P$2") (pinfunction "2_P$2") (pintype "passive"))
      (node (ref "C22") (pin "P$2") (pinfunction "2_P$2") (pintype "passive"))
      (node (ref "C23") (pin "2") (pinfunction "2_2") (pintype "passive"))
      (node (ref "C24") (pin "P$2") (pinfunction "2_P$2") (pintype "passive"))
      (node (ref "C25") (pin "P$2") (pinfunction "2_P$2") (pintype "passive"))
      (node (ref "C26") (pin "2") (pinfunction "2_2") (pintype "passive"))
      (node (ref "C27") (pin "P$2") (pinfunction "2_P$2") (pintype "passive"))
      (node (ref "C28") (pin "2") (pinfunction "2_2") (pintype "passive"))
      (node (ref "C29") (pin "P$2") (pinfunction "2_P$2") (pintype "passive"))
      (node (ref "C30") (pin "P$1") (pinfunction "1_P$1") (pintype "passive"))
      (node (ref "C31") (pin "P$2") (pinfunction "2_P$2") (pintype "passive"))
      (node (ref "C32") (pin "P$2") (pinfunction "2_P$2") (pintype "passive"))
      (node (ref "C34") (pin "P$1") (pinfunction "1_P$1") (pintype "passive"))
      (node (ref "C35") (pin "P$2") (pinfunction "2_P$2") (pintype "passive"))
      (node (ref "C36") (pin "P$1") (pinfunction "1_P$1") (pintype "passive"))
      (node (ref "C37") (pin "P$1") (pinfunction "1_P$1") (pintype "passive"))
      (node (ref "C38") (pin "P$2") (pinfunction "2_P$2") (pintype "passive"))
      (node (ref "C39") (pin "P$2") (pinfunction "2_P$2") (pintype "passive"))
      (node (ref "C40") (pin "P$2") (pinfunction "2_P$2") (pintype "passive"))
      (node (ref "C41") (pin "P$2") (pinfunction "2_P$2") (pintype "passive"))
      (node (ref "C42") (pin "P$2") (pinfunction "2_P$2") (pintype "passive"))
      (node (ref "C43") (pin "2") (pinfunction "2_2") (pintype "passive"))
      (node (ref "C44") (pin "P$2") (pinfunction "2_P$2") (pintype "passive"))
      (node (ref "C45") (pin "P$2") (pinfunction "2_P$2") (pintype "passive"))
      (node (ref "C46") (pin "P$2") (pinfunction "2_P$2") (pintype "passive"))
      (node (ref "C47") (pin "P$2") (pinfunction "2_P$2") (pintype "passive"))
      (node (ref "C48") (pin "2") (pinfunction "2_2") (pintype "passive"))
      (node (ref "C49") (pin "P$2") (pinfunction "2_P$2") (pintype "passive"))
      (node (ref "C5") (pin "P$2") (pinfunction "2_P$2") (pintype "passive"))
      (node (ref "C50") (pin "P$2") (pinfunction "2_P$2") (pintype "passive"))
      (node (ref "C51") (pin "P$2") (pinfunction "2_P$2") (pintype "passive"))
      (node (ref "C52") (pin "P$2") (pinfunction "2_P$2") (pintype "passive"))
      (node (ref "C53") (pin "P$2") (pinfunction "2_P$2") (pintype "passive"))
      (node (ref "C54") (pin "P$1") (pinfunction "1_P$1") (pintype "passive"))
      (node (ref "C55") (pin "P$1") (pinfunction "1_P$1") (pintype "passive"))
      (node (ref "C56") (pin "P$1") (pinfunction "1_P$1") (pintype "passive"))
      (node (ref "C57") (pin "P$2") (pinfunction "2_P$2") (pintype "passive"))
      (node (ref "C58") (pin "P$2") (pinfunction "2_P$2") (pintype "passive"))
      (node (ref "C59") (pin "P$2") (pinfunction "2_P$2") (pintype "passive"))
      (node (ref "C6") (pin "P$1") (pinfunction "1_P$1") (pintype "passive"))
      (node (ref "C60") (pin "P$2") (pinfunction "2_P$2") (pintype "passive"))
      (node (ref "C61") (pin "P$1") (pinfunction "1_P$1") (pintype "passive"))
      (node (ref "C62") (pin "P$2") (pinfunction "2_P$2") (pintype "passive"))
      (node (ref "C63") (pin "P$2") (pinfunction "2_P$2") (pintype "passive"))
      (node (ref "C64") (pin "P$1") (pinfunction "1_P$1") (pintype "passive"))
      (node (ref "C65") (pin "P$2") (pinfunction "2_P$2") (pintype "passive"))
      (node (ref "C7") (pin "P$1") (pinfunction "1_P$1") (pintype "passive"))
      (node (ref "C8") (pin "P$2") (pinfunction "2_P$2") (pintype "passive"))
      (node (ref "IC3") (pin "2") (pinfunction "GND_2") (pintype "power_in"))
      (node (ref "IC4") (pin "2") (pinfunction "GND_2") (pintype "power_in"))
      (node (ref "J1") (pin "P$19") (pinfunction "P$19_P$19") (pintype "bidirectional"))
      (node (ref "J11") (pin "10") (pinfunction "10_10") (pintype "passive"))
      (node (ref "J11") (pin "6") (pinfunction "6_6") (pintype "passive"))
      (node (ref "J11") (pin "8") (pinfunction "8_8") (pintype "passive"))
      (node (ref "J12") (pin "P$14") (pinfunction "GND_P$14") (pintype "power_in"))
      (node (ref "J12") (pin "P$20") (pinfunction "GND_P$20") (pintype "power_in"))
      (node (ref "J12") (pin "P$25") (pinfunction "GND_P$25") (pintype "power_in"))
      (node (ref "J12") (pin "P$30") (pinfunction "GND_P$30") (pintype "power_in"))
      (node (ref "J12") (pin "P$34") (pinfunction "GND_P$34") (pintype "power_in"))
      (node (ref "J12") (pin "P$39") (pinfunction "GND_P$39") (pintype "power_in"))
      (node (ref "J12") (pin "P$6") (pinfunction "GND_P$6") (pintype "power_in"))
      (node (ref "J12") (pin "P$9") (pinfunction "GND_P$9") (pintype "power_in"))
      (node (ref "J3") (pin "GND") (pinfunction "GND_GND") (pintype "power_in"))
      (node (ref "J4") (pin "10") (pinfunction "GLO_10") (pintype "bidirectional"))
      (node (ref "J4") (pin "8") (pinfunction "P8_8") (pintype "bidirectional"))
      (node (ref "LED3") (pin "C") (pinfunction "C_C") (pintype "passive"))
      (node (ref "LED4") (pin "C") (pinfunction "C_C") (pintype "passive"))
      (node (ref "R14") (pin "P$1") (pinfunction "1_P$1") (pintype "passive"))
      (node (ref "R16") (pin "P$1") (pinfunction "1_P$1") (pintype "passive"))
      (node (ref "R17") (pin "P$1") (pinfunction "1_P$1") (pintype "passive"))
      (node (ref "R19") (pin "P$1") (pinfunction "1_P$1") (pintype "passive"))
      (node (ref "R21") (pin "P$1") (pinfunction "1_P$1") (pintype "passive"))
      (node (ref "R25") (pin "P$1") (pinfunction "1_P$1") (pintype "passive"))
      (node (ref "R34") (pin "P$1") (pinfunction "1_P$1") (pintype "passive"))
      (node (ref "R4") (pin "P$2") (pinfunction "2_P$2") (pintype "passive"))
      (node (ref "U$2") (pin "P1") (pinfunction "GND_P1") (pintype "bidirectional"))
      (node (ref "U$2") (pin "P21") (pinfunction "GND1_P21") (pintype "bidirectional"))
      (node (ref "U$2") (pin "P23") (pinfunction "GND2_P23") (pintype "bidirectional"))
      (node (ref "U$3") (pin "2") (pinfunction "2_2") (pintype "bidirectional"))
      (node (ref "U$3") (pin "4") (pinfunction "4_4") (pintype "bidirectional"))
      (node (ref "U$4") (pin "P$2") (pinfunction "2_P$2") (pintype "passive"))
      (node (ref "U$7") (pin "P$2") (pinfunction "P$2_P$2") (pintype "bidirectional"))
      (node (ref "U$8") (pin "N-") (pinfunction "-_N-") (pintype "passive"))
      (node (ref "U1") (pin "15") (pinfunction "~_15") (pintype "passive"))
      (node (ref "U1") (pin "9") (pinfunction "~{_4}_9") (pintype "passive"))
      (node (ref "U2") (pin "2") (pinfunction "GND_2") (pintype "input"))
      (node (ref "U3") (pin "22") (pinfunction "GND_22") (pintype "power_in"))
      (node (ref "U3") (pin "25") (pinfunction "25_25") (pintype "passive"))
      (node (ref "U4") (pin "111") (pinfunction "VSS(IO)5_111") (pintype "bidirectional"))
      (node (ref "U4") (pin "124") (pinfunction "VSS(IO)6_124") (pintype "bidirectional"))
      (node (ref "U4") (pin "139") (pinfunction "VSS(IO)7_139") (pintype "bidirectional"))
      (node (ref "U4") (pin "150") (pinfunction "VSS(IO)8_150") (pintype "bidirectional"))
      (node (ref "U4") (pin "153") (pinfunction "VREFL_153") (pintype "bidirectional"))
      (node (ref "U4") (pin "156") (pinfunction "AVSS0_156") (pintype "bidirectional"))
      (node (ref "U4") (pin "157") (pinfunction "VREFL0_157") (pintype "bidirectional"))
      (node (ref "U4") (pin "170") (pinfunction "VSS(IO)9_170") (pintype "bidirectional"))
      (node (ref "U4") (pin "22") (pinfunction "VSS1_22") (pintype "bidirectional"))
      (node (ref "U4") (pin "28") (pinfunction "AVSS_USBHS_28") (pintype "bidirectional"))
      (node (ref "U4") (pin "29") (pinfunction "PVSS_USBHS_29") (pintype "bidirectional"))
      (node (ref "U4") (pin "30") (pinfunction "VSS2_USBHS_30") (pintype "bidirectional"))
      (node (ref "U4") (pin "33") (pinfunction "VSS1_USBHS_33") (pintype "bidirectional"))
      (node (ref "U4") (pin "35") (pinfunction "VSSIO_35") (pintype "bidirectional"))
      (node (ref "U4") (pin "45") (pinfunction "VSS_USB_45") (pintype "bidirectional"))
      (node (ref "U4") (pin "60") (pinfunction "VSS(IO)2_60") (pintype "bidirectional"))
      (node (ref "U4") (pin "63") (pinfunction "VSS(IO/DCDC)_63") (pintype "bidirectional"))
      (node (ref "U4") (pin "66") (pinfunction "VCC_DCDC(IO/DCDC)_66") (pintype "bidirectional"))
      (node (ref "U4") (pin "83") (pinfunction "VSS(IO)3_83") (pintype "bidirectional"))
      (node (ref "U4") (pin "98") (pinfunction "VSS(IO)4_98") (pintype "bidirectional"))
      (node (ref "U5") (pin "P$3") (pinfunction "VOUT-_P$3") (pintype "bidirectional"))
      (node (ref "U5") (pin "P$6") (pinfunction "AC_N_P$6") (pintype "bidirectional"))
      (node (ref "U6") (pin "2") (pinfunction "REF_2") (pintype "passive"))
      (node (ref "U6") (pin "3") (pinfunction "VS-_3") (pintype "power_in"))
      (node (ref "U7") (pin "2") (pinfunction "REF_2") (pintype "passive"))
      (node (ref "U7") (pin "3") (pinfunction "VS-_3") (pintype "power_in"))
      (node (ref "X4") (pin "2") (pinfunction "2_2") (pintype "bidirectional"))
      (node (ref "X4") (pin "4") (pinfunction "4_4") (pintype "bidirectional"))
    )
    (net (code "32") (name "GND2") (class "Default")
      (node (ref "C3") (pin "P$2") (pinfunction "2_P$2") (pintype "passive"))
      (node (ref "C4") (pin "P$2") (pinfunction "2_P$2") (pintype "passive"))
      (node (ref "J2") (pin "P$5") (pinfunction "GND_P$5") (pintype "bidirectional"))
      (node (ref "LED1") (pin "C") (pinfunction "C_C") (pintype "passive"))
      (node (ref "U1") (pin "2") (pinfunction "~{_2}_2") (pintype "passive"))
      (node (ref "U1") (pin "8") (pinfunction "~{_3}_8") (pintype "passive"))
    )
    (net (code "33") (name "GNDE") (class "Default")
      (node (ref "C16") (pin "P$2") (pinfunction "2_P$2") (pintype "passive"))
      (node (ref "C64") (pin "P$2") (pinfunction "2_P$2") (pintype "passive"))
      (node (ref "J2") (pin "P$6") (pinfunction "SHIELD1_P$6") (pintype "bidirectional"))
      (node (ref "J2") (pin "P$7") (pinfunction "SHIELD2_P$7") (pintype "bidirectional"))
      (node (ref "J2") (pin "P$8") (pinfunction "SHIELD3_P$8") (pintype "bidirectional"))
      (node (ref "J2") (pin "P$9") (pinfunction "SHIELD4_P$9") (pintype "bidirectional"))
      (node (ref "J3") (pin "SHLD1") (pinfunction "SHIELD_1_SHLD1") (pintype "bidirectional"))
      (node (ref "J3") (pin "SHLD2") (pinfunction "SHIELD_2_SHLD2") (pintype "bidirectional"))
      (node (ref "J4") (pin "13") (pinfunction "GNDE0_13") (pintype "bidirectional"))
      (node (ref "J4") (pin "14") (pinfunction "GNDE1_14") (pintype "bidirectional"))
      (node (ref "R4") (pin "P$1") (pinfunction "1_P$1") (pintype "passive"))
    )
    (net (code "34") (name "GP4") (class "Default")
      (node (ref "J12") (pin "P$7") (pinfunction "GP4_P$7") (pintype "bidirectional"))
      (node (ref "U4") (pin "49") (pinfunction "P2_7_49") (pintype "bidirectional"))
    )
    (net (code "35") (name "GP5") (class "Default")
      (node (ref "J12") (pin "P$29") (pinfunction "GP5_P$29") (pintype "bidirectional"))
      (node (ref "U4") (pin "57") (pinfunction "P3_15_57") (pintype "bidirectional"))
    )
    (net (code "36") (name "GP6") (class "Default")
      (node (ref "J12") (pin "P$31") (pinfunction "GP6_P$31") (pintype "bidirectional"))
      (node (ref "U4") (pin "59") (pinfunction "P9_1_59") (pintype "bidirectional"))
    )
    (net (code "37") (name "GP12") (class "Default")
      (node (ref "J12") (pin "P$32") (pinfunction "GP12_P$32") (pintype "bidirectional"))
      (node (ref "U4") (pin "58") (pinfunction "P9_0_58") (pintype "bidirectional"))
    )
    (net (code "38") (name "GP13") (class "Default")
      (node (ref "J12") (pin "P$33") (pinfunction "GP13_P$33") (pintype "bidirectional"))
      (node (ref "U4") (pin "76") (pinfunction "P3_10_76") (pintype "bidirectional"))
    )
    (net (code "39") (name "GP14") (class "Default")
      (node (ref "J12") (pin "P$8") (pinfunction "TXO_P$8") (pintype "output"))
      (node (ref "U4") (pin "42") (pinfunction "P4_9_42") (pintype "bidirectional"))
    )
    (net (code "40") (name "GP15") (class "Default")
      (node (ref "J12") (pin "P$10") (pinfunction "RXI_P$10") (pintype "input"))
      (node (ref "U4") (pin "43") (pinfunction "P4_8_43") (pintype "bidirectional"))
    )
    (net (code "41") (name "GP16") (class "Default")
      (node (ref "J12") (pin "P$36") (pinfunction "GP16_P$36") (pintype "bidirectional"))
      (node (ref "U4") (pin "79") (pinfunction "P3_7_79") (pintype "bidirectional"))
    )
    (net (code "42") (name "GP17") (class "Default")
      (node (ref "J12") (pin "P$11") (pinfunction "GP17_P$11") (pintype "bidirectional"))
      (node (ref "U4") (pin "51") (pinfunction "P2_5_51") (pintype "bidirectional"))
    )
    (net (code "43") (name "GP18") (class "Default")
      (node (ref "J12") (pin "P$12") (pinfunction "GP18#_P$12") (pintype "bidirectional"))
      (node (ref "U4") (pin "50") (pinfunction "P2_6_50") (pintype "bidirectional"))
    )
    (net (code "44") (name "GP19") (class "Default")
      (node (ref "J12") (pin "P$35") (pinfunction "GP19_P$35") (pintype "bidirectional"))
      (node (ref "U4") (pin "77") (pinfunction "P3_9_77") (pintype "bidirectional"))
    )
    (net (code "45") (name "GP20") (class "Default")
      (node (ref "J12") (pin "P$38") (pinfunction "GP20_P$38") (pintype "bidirectional"))
      (node (ref "U4") (pin "81") (pinfunction "P3_5_81") (pintype "bidirectional"))
    )
    (net (code "46") (name "GP21") (class "Default")
      (node (ref "J12") (pin "P$40") (pinfunction "GP21_P$40") (pintype "bidirectional"))
      (node (ref "U4") (pin "82") (pinfunction "P3_4_82") (pintype "bidirectional"))
    )
    (net (code "47") (name "GP22") (class "Default")
      (node (ref "J12") (pin "P$15") (pinfunction "GP22_P$15") (pintype "bidirectional"))
      (node (ref "U4") (pin "72") (pinfunction "P9_6_72") (pintype "bidirectional"))
    )
    (net (code "48") (name "GP23") (class "Default")
      (node (ref "J12") (pin "P$16") (pinfunction "GP23_P$16") (pintype "bidirectional"))
      (node (ref "U4") (pin "71") (pinfunction "P9_7_71") (pintype "bidirectional"))
    )
    (net (code "49") (name "GP24") (class "Default")
      (node (ref "J12") (pin "P$18") (pinfunction "GP24_P$18") (pintype "bidirectional"))
      (node (ref "U4") (pin "73") (pinfunction "P9_5_73") (pintype "bidirectional"))
    )
    (net (code "50") (name "GP25") (class "Default")
      (node (ref "J12") (pin "P$22") (pinfunction "GP25_P$22") (pintype "bidirectional"))
      (node (ref "U4") (pin "56") (pinfunction "P3_14_56") (pintype "bidirectional"))
    )
    (net (code "51") (name "GP26") (class "Default")
      (node (ref "J12") (pin "P$37") (pinfunction "GP26_P$37") (pintype "bidirectional"))
      (node (ref "U4") (pin "80") (pinfunction "P3_6_80") (pintype "bidirectional"))
    )
    (net (code "52") (name "GP27") (class "Default")
      (node (ref "J12") (pin "P$13") (pinfunction "GP27_P$13") (pintype "bidirectional"))
      (node (ref "U4") (pin "70") (pinfunction "P9_8_70") (pintype "bidirectional"))
    )
    (net (code "53") (name "ID_SC") (class "Default")
      (node (ref "J12") (pin "P$28") (pinfunction "ID_SC_P$28") (pintype "bidirectional"))
      (node (ref "U4") (pin "93") (pinfunction "P1_12_93") (pintype "bidirectional"))
    )
    (net (code "54") (name "ID_SD") (class "Default")
      (node (ref "J12") (pin "P$27") (pinfunction "ID_SD_P$27") (pintype "bidirectional"))
      (node (ref "U4") (pin "92") (pinfunction "P1_11_92") (pintype "bidirectional"))
    )
    (net (code "55") (name "IIC_0_SCL") (class "Default")
      (node (ref "J12") (pin "P$5") (pinfunction "SCL_P$5") (pintype "bidirectional"))
      (node (ref "U4") (pin "1") (pinfunction "P4_0_1") (pintype "bidirectional"))
    )
    (net (code "56") (name "IIC_0_SDA") (class "Default")
      (node (ref "J12") (pin "P$3") (pinfunction "SDA_P$3") (pintype "bidirectional"))
      (node (ref "U4") (pin "2") (pinfunction "P4_1_2") (pintype "bidirectional"))
    )
    (net (code "57") (name "IRQ0") (class "Default")
      (node (ref "U$2") (pin "P10") (pinfunction "IRQ0_P10") (pintype "bidirectional"))
      (node (ref "U4") (pin "86") (pinfunction "P3_2_86") (pintype "bidirectional"))
    )
    (net (code "58") (name "IRQ1") (class "Default")
      (node (ref "U$2") (pin "P11") (pinfunction "IRQ1_P11") (pintype "bidirectional"))
      (node (ref "U4") (pin "87") (pinfunction "P3_1_87") (pintype "bidirectional"))
    )
    (net (code "59") (name "LED1{slash}SPEED") (class "Default")
      (node (ref "J4") (pin "11") (pinfunction "YLO_11") (pintype "bidirectional"))
      (node (ref "U3") (pin "23") (pinfunction "LED0/ANEN_SPEED_23") (pintype "bidirectional"))
    )
    (net (code "60") (name "M0_STEP") (class "Default")
      (node (ref "U4") (pin "16") (pinfunction "PB_0_16") (pintype "bidirectional"))
    )
    (net (code "61") (name "NC") (class "Default")
      (node (ref "J4") (pin "7") (pinfunction "P7_7") (pintype "bidirectional"))
    )
    (net (code "62") (name "Net-(C3-1)") (class "Default")
      (node (ref "C3") (pin "P$1") (pinfunction "1_P$1") (pintype "passive"))
      (node (ref "U1") (pin "3") (pinfunction "VDD1_3") (pintype "power_in"))
      (node (ref "U1") (pin "4") (pinfunction "PDEN_4") (pintype "passive"))
      (node (ref "U1") (pin "5") (pinfunction "SPU_5") (pintype "passive"))
    )
    (net (code "63") (name "Net-(C7-2)") (class "Default")
      (node (ref "C7") (pin "P$2") (pinfunction "2_P$2") (pintype "passive"))
      (node (ref "U1") (pin "12") (pinfunction "PIN_12") (pintype "passive"))
      (node (ref "U1") (pin "13") (pinfunction "SPD_13") (pintype "passive"))
      (node (ref "U1") (pin "14") (pinfunction "VDD2_14") (pintype "power_in"))
    )
    (net (code "64") (name "Net-(C31-1)") (class "Default")
      (node (ref "C31") (pin "P$1") (pinfunction "1_P$1") (pintype "passive"))
      (node (ref "U4") (pin "62") (pinfunction "VCL1_62") (pintype "bidirectional"))
    )
    (net (code "65") (name "Net-(C37-2)") (class "Default")
      (node (ref "C37") (pin "P$2") (pinfunction "2_P$2") (pintype "passive"))
      (node (ref "U4") (pin "148") (pinfunction "VCL2_148") (pintype "bidirectional"))
    )
    (net (code "66") (name "Net-(C38-1)") (class "Default")
      (node (ref "C38") (pin "P$1") (pinfunction "1_P$1") (pintype "passive"))
      (node (ref "U4") (pin "19") (pinfunction "VCLO_19") (pintype "bidirectional"))
    )
    (net (code "67") (name "Net-(C44-1)") (class "Default")
      (node (ref "C43") (pin "1") (pinfunction "1_1") (pintype "passive"))
      (node (ref "C44") (pin "P$1") (pinfunction "1_P$1") (pintype "passive"))
      (node (ref "FB2/2") (pin "2") (pinfunction "P$2_2") (pintype "bidirectional"))
      (node (ref "U3") (pin "2") (pinfunction "VDDA_3.3_2") (pintype "power_in"))
    )
    (net (code "68") (name "Net-(J2-D+)") (class "Default")
      (node (ref "J2") (pin "P$3") (pinfunction "D+_P$3") (pintype "bidirectional"))
      (node (ref "R2") (pin "P$2") (pinfunction "2_P$2") (pintype "passive"))
    )
    (net (code "69") (name "Net-(J2-D-)") (class "Default")
      (node (ref "J2") (pin "P$2") (pinfunction "D-_P$2") (pintype "bidirectional"))
      (node (ref "R3") (pin "P$2") (pinfunction "2_P$2") (pintype "passive"))
    )
    (net (code "70") (name "Net-(R2-1)") (class "Default")
      (node (ref "R2") (pin "P$1") (pinfunction "1_P$1") (pintype "passive"))
      (node (ref "U1") (pin "7") (pinfunction "UD+_7") (pintype "passive"))
    )
    (net (code "71") (name "Net-(R3-1)") (class "Default")
      (node (ref "R3") (pin "P$1") (pinfunction "1_P$1") (pintype "passive"))
      (node (ref "U1") (pin "6") (pinfunction "UD_6") (pintype "passive"))
    )
    (net (code "72") (name "Net-(R5-2)") (class "Default")
      (node (ref "R5") (pin "P$2") (pinfunction "2_P$2") (pintype "passive"))
      (node (ref "U1") (pin "11") (pinfunction "DD_11") (pintype "passive"))
    )
    (net (code "73") (name "Net-(R6-2)") (class "Default")
      (node (ref "R6") (pin "P$2") (pinfunction "2_P$2") (pintype "passive"))
      (node (ref "U1") (pin "10") (pinfunction "DD+_10") (pintype "passive"))
    )
    (net (code "74") (name "Net-(R8-2)") (class "Default")
      (node (ref "LED3") (pin "A") (pinfunction "A_A") (pintype "passive"))
      (node (ref "R8") (pin "P$2") (pinfunction "2_P$2") (pintype "passive"))
    )
    (net (code "75") (name "Net-(R9-2)") (class "Default")
      (node (ref "LED4") (pin "A") (pinfunction "A_A") (pintype "passive"))
      (node (ref "R9") (pin "P$2") (pinfunction "2_P$2") (pintype "passive"))
    )
    (net (code "76") (name "Net-(R10-1)") (class "Default")
      (node (ref "LED1") (pin "A") (pinfunction "A_A") (pintype "passive"))
      (node (ref "R10") (pin "P$1") (pinfunction "1_P$1") (pintype "passive"))
    )
    (net (code "77") (name "Net-(R16-2)") (class "Default")
      (node (ref "R16") (pin "P$2") (pinfunction "2_P$2") (pintype "passive"))
      (node (ref "U4") (pin "65") (pinfunction "VLO2(DCDC)_65") (pintype "bidirectional"))
    )
    (net (code "78") (name "Net-(R17-2)") (class "Default")
      (node (ref "R17") (pin "P$2") (pinfunction "2_P$2") (pintype "passive"))
      (node (ref "U4") (pin "64") (pinfunction "VLO1(DCDC)_64") (pintype "bidirectional"))
    )
    (net (code "79") (name "Net-(R19-2)") (class "Default")
      (node (ref "R19") (pin "P$2") (pinfunction "2_P$2") (pintype "passive"))
      (node (ref "U4") (pin "27") (pinfunction "USBHS_RREF_27") (pintype "bidirectional"))
    )
    (net (code "80") (name "P0_02") (class "Default")
      (node (ref "J1") (pin "P$6") (pinfunction "P$6_P$6") (pintype "bidirectional"))
      (node (ref "U4") (pin "167") (pinfunction "P0_2/AN002_167") (pintype "bidirectional"))
    )
    (net (code "81") (name "P0_03") (class "Default")
      (node (ref "J1") (pin "P$5") (pinfunction "P$5_P$5") (pintype "bidirectional"))
      (node (ref "U4") (pin "166") (pinfunction "P0_3/PGAVSS000_166") (pintype "bidirectional"))
    )
    (net (code "82") (name "P0_04") (class "Default")
      (node (ref "J1") (pin "P$8") (pinfunction "P$8_P$8") (pintype "bidirectional"))
      (node (ref "U4") (pin "165") (pinfunction "P0_4/AN100_165") (pintype "bidirectional"))
    )
    (net (code "83") (name "P0_07") (class "Default")
      (node (ref "J1") (pin "P$7") (pinfunction "P$7_P$7") (pintype "bidirectional"))
      (node (ref "U4") (pin "162") (pinfunction "P0_7/PGVSS100_162") (pintype "bidirectional"))
    )
    (net (code "84") (name "P0_14") (class "Default")
      (node (ref "J1") (pin "P$10") (pinfunction "P$10_P$10") (pintype "bidirectional"))
      (node (ref "U4") (pin "152") (pinfunction "P0_14/DA0/AN005/AN105_152") (pintype "bidirectional"))
    )
    (net (code "85") (name "P0_15") (class "Default")
      (node (ref "J1") (pin "P$9") (pinfunction "P$9_P$9") (pintype "bidirectional"))
      (node (ref "U4") (pin "151") (pinfunction "P0_15/DA1/AN006/AN106_151") (pintype "bidirectional"))
    )
    (net (code "86") (name "P1_05") (class "Default")
      (node (ref "U4") (pin "127") (pinfunction "P1_5_127") (pintype "bidirectional"))
    )
    (net (code "87") (name "P1_13") (class "Default")
      (node (ref "U4") (pin "94") (pinfunction "P1_13_94") (pintype "bidirectional"))
    )
    (net (code "88") (name "P1_14") (class "Default")
      (node (ref "U4") (pin "95") (pinfunction "P1_14_95") (pintype "bidirectional"))
    )
    (net (code "89") (name "P1_15") (class "Default")
      (node (ref "U4") (pin "96") (pinfunction "P1_15_96") (pintype "bidirectional"))
    )
    (net (code "90") (name "P2_00") (class "Default")
      (node (ref "U4") (pin "69") (pinfunction "P2_0(INPUT_ONLY)_69") (pintype "bidirectional"))
    )
    (net (code "91") (name "P2_01") (class "Default")
      (node (ref "U4") (pin "68") (pinfunction "P2_1/MD_68") (pintype "bidirectional"))
    )
    (net (code "92") (name "P3_03") (class "Default")
      (node (ref "U4") (pin "85") (pinfunction "P3_3_85") (pintype "bidirectional"))
    )
    (net (code "93") (name "P3_11") (class "Default")
      (node (ref "U4") (pin "75") (pinfunction "P3_11_75") (pintype "bidirectional"))
    )
    (net (code "94") (name "P4_02") (class "Default")
      (node (ref "U4") (pin "3") (pinfunction "P4_2_3") (pintype "bidirectional"))
    )
    (net (code "95") (name "P4_10") (class "Default")
      (node (ref "U4") (pin "41") (pinfunction "P4_10_41") (pintype "bidirectional"))
    )
    (net (code "96") (name "P4_11") (class "Default")
      (node (ref "U4") (pin "40") (pinfunction "P4_11_40") (pintype "bidirectional"))
    )
    (net (code "97") (name "P4_12") (class "Default")
      (node (ref "U4") (pin "39") (pinfunction "P4_12_39") (pintype "bidirectional"))
    )
    (net (code "98") (name "P4_13") (class "Default")
      (node (ref "U4") (pin "38") (pinfunction "P4_13_38") (pintype "bidirectional"))
    )
    (net (code "99") (name "P4_14") (class "Default")
      (node (ref "U4") (pin "37") (pinfunction "P4_14_37") (pintype "bidirectional"))
    )
    (net (code "100") (name "P4_15") (class "Default")
      (node (ref "U4") (pin "36") (pinfunction "P4_15_36") (pintype "bidirectional"))
    )
    (net (code "101") (name "P5_00") (class "Default")
      (node (ref "J1") (pin "P$17") (pinfunction "P$17_P$17") (pintype "bidirectional"))
      (node (ref "U4") (pin "140") (pinfunction "P5_0/AN016_140") (pintype "bidirectional"))
    )
    (net (code "102") (name "P5_01") (class "Default")
      (node (ref "J1") (pin "P$18") (pinfunction "P$18_P$18") (pintype "bidirectional"))
      (node (ref "U4") (pin "141") (pinfunction "P5_1/AN116_141") (pintype "bidirectional"))
    )
    (net (code "103") (name "P5_02") (class "Default")
      (node (ref "J1") (pin "P$15") (pinfunction "P$15_P$15") (pintype "bidirectional"))
      (node (ref "U4") (pin "142") (pinfunction "P5_2/AN017_142") (pintype "bidirectional"))
    )
    (net (code "104") (name "P5_03") (class "Default")
      (node (ref "J1") (pin "P$16") (pinfunction "P$16_P$16") (pintype "bidirectional"))
      (node (ref "U4") (pin "143") (pinfunction "P5_3/AN117_143") (pintype "bidirectional"))
    )
    (net (code "105") (name "P5_04") (class "Default")
      (node (ref "J1") (pin "P$13") (pinfunction "P$13_P$13") (pintype "bidirectional"))
      (node (ref "U4") (pin "144") (pinfunction "P5_4/AN018_144") (pintype "bidirectional"))
    )
    (net (code "106") (name "P5_05") (class "Default")
      (node (ref "J1") (pin "P$14") (pinfunction "P$14_P$14") (pintype "bidirectional"))
      (node (ref "U4") (pin "145") (pinfunction "P5_5/AN118_145") (pintype "bidirectional"))
    )
    (net (code "107") (name "P5_06") (class "Default")
      (node (ref "J1") (pin "P$11") (pinfunction "P$11_P$11") (pintype "bidirectional"))
      (node (ref "U4") (pin "146") (pinfunction "P5_6/AN019_146") (pintype "bidirectional"))
    )
    (net (code "108") (name "P5_07") (class "Default")
      (node (ref "J1") (pin "P$12") (pinfunction "P$12_P$12") (pintype "bidirectional"))
      (node (ref "U4") (pin "147") (pinfunction "P5_7/AN119_147") (pintype "bidirectional"))
    )
    (net (code "109") (name "P5_11") (class "Default")
      (node (ref "J1") (pin "P$2") (pinfunction "P$2_P$2") (pintype "bidirectional"))
      (node (ref "U4") (pin "176") (pinfunction "P5_11_176") (pintype "bidirectional"))
    )
    (net (code "110") (name "P5_12") (class "Default")
      (node (ref "J1") (pin "P$1") (pinfunction "P$1_P$1") (pintype "bidirectional"))
      (node (ref "U4") (pin "175") (pinfunction "P5_12_175") (pintype "bidirectional"))
    )
    (net (code "111") (name "P5_13") (class "Default")
      (node (ref "J1") (pin "P$4") (pinfunction "P$4_P$4") (pintype "bidirectional"))
      (node (ref "U4") (pin "174") (pinfunction "P5_13_174") (pintype "bidirectional"))
    )
    (net (code "112") (name "P6_02") (class "Default")
      (node (ref "U4") (pin "120") (pinfunction "P6_2_120") (pintype "bidirectional"))
    )
    (net (code "113") (name "P6_03") (class "Default")
      (node (ref "U4") (pin "119") (pinfunction "P6_3_119") (pintype "bidirectional"))
    )
    (net (code "114") (name "P6_04") (class "Default")
      (node (ref "U4") (pin "118") (pinfunction "P6_4_118") (pintype "bidirectional"))
    )
    (net (code "115") (name "P6_05") (class "Default")
      (node (ref "U4") (pin "117") (pinfunction "P6_5_117") (pintype "bidirectional"))
    )
    (net (code "116") (name "P6_06") (class "Default")
      (node (ref "U4") (pin "116") (pinfunction "P6_6_116") (pintype "bidirectional"))
    )
    (net (code "117") (name "P6_07") (class "Default")
      (node (ref "U4") (pin "115") (pinfunction "P6_7_115") (pintype "bidirectional"))
    )
    (net (code "118") (name "P6_08") (class "Default")
      (node (ref "U4") (pin "99") (pinfunction "P6_8_99") (pintype "bidirectional"))
    )
    (net (code "119") (name "P6_09") (class "Default")
      (node (ref "U4") (pin "100") (pinfunction "P6_9_100") (pintype "bidirectional"))
    )
    (net (code "120") (name "P6_10") (class "Default")
      (node (ref "U4") (pin "101") (pinfunction "P6_10_101") (pintype "bidirectional"))
    )
    (net (code "121") (name "P6_11") (class "Default")
      (node (ref "U4") (pin "102") (pinfunction "P6_11_102") (pintype "bidirectional"))
    )
    (net (code "122") (name "P6_12") (class "Default")
      (node (ref "U4") (pin "103") (pinfunction "P6_12_103") (pintype "bidirectional"))
    )
    (net (code "123") (name "P6_13") (class "Default")
      (node (ref "U4") (pin "104") (pinfunction "P6_13_104") (pintype "bidirectional"))
    )
    (net (code "124") (name "P6_14") (class "Default")
      (node (ref "U4") (pin "105") (pinfunction "P6_14_105") (pintype "bidirectional"))
    )
    (net (code "125") (name "P6_15") (class "Default")
      (node (ref "U4") (pin "106") (pinfunction "P6_15_106") (pintype "bidirectional"))
    )
    (net (code "126") (name "P7_06") (class "Default")
      (node (ref "U4") (pin "14") (pinfunction "P7_6_14") (pintype "bidirectional"))
    )
    (net (code "127") (name "P7_07") (class "Default")
      (node (ref "U4") (pin "15") (pinfunction "P7_7_15") (pintype "bidirectional"))
    )
    (net (code "128") (name "P8_03") (class "Default")
      (node (ref "U4") (pin "136") (pinfunction "P8_3_136") (pintype "bidirectional"))
    )
    (net (code "129") (name "P8_04") (class "Default")
      (node (ref "U4") (pin "137") (pinfunction "P8_4_137") (pintype "bidirectional"))
    )
    (net (code "130") (name "P8_05") (class "Default")
      (node (ref "J1") (pin "P$3") (pinfunction "P$3_P$3") (pintype "bidirectional"))
      (node (ref "U4") (pin "173") (pinfunction "P8_5_173") (pintype "bidirectional"))
    )
    (net (code "131") (name "PA_00") (class "Default")
      (node (ref "U4") (pin "114") (pinfunction "PA_0_114") (pintype "bidirectional"))
    )
    (net (code "132") (name "PA_01") (class "Default")
      (node (ref "U4") (pin "113") (pinfunction "PA_1_113") (pintype "bidirectional"))
    )
    (net (code "133") (name "PA_08") (class "Default")
      (node (ref "U4") (pin "107") (pinfunction "PA_8_107") (pintype "bidirectional"))
    )
    (net (code "134") (name "PA_09") (class "Default")
      (node (ref "U4") (pin "108") (pinfunction "PA_9_108") (pintype "bidirectional"))
    )
    (net (code "135") (name "PA_10") (class "Default")
      (node (ref "U4") (pin "109") (pinfunction "PA_10_109") (pintype "bidirectional"))
    )
    (net (code "136") (name "PM0") (class "Default")
      (node (ref "U$2") (pin "P12") (pinfunction "PM0_P12") (pintype "bidirectional"))
      (node (ref "U4") (pin "126") (pinfunction "P1_6_126") (pintype "bidirectional"))
    )
    (net (code "137") (name "PM1") (class "Default")
      (node (ref "U$2") (pin "P13") (pinfunction "PM1_P13") (pintype "bidirectional"))
      (node (ref "U4") (pin "125") (pinfunction "P1_7_125") (pintype "bidirectional"))
    )
    (net (code "138") (name "R51") (class "Default")
      (node (ref "J4") (pin "12") (pinfunction "YHI_12") (pintype "bidirectional"))
      (node (ref "R23") (pin "P$1") (pinfunction "1_P$1") (pintype "passive"))
    )
    (net (code "139") (name "R52") (class "Default")
      (node (ref "J4") (pin "9") (pinfunction "GHI_9") (pintype "bidirectional"))
      (node (ref "R24") (pin "P$1") (pinfunction "1_P$1") (pintype "passive"))
    )
    (net (code "140") (name "RESET") (class "Default")
      (node (ref "C57") (pin "P$1") (pinfunction "1_P$1") (pintype "passive"))
      (node (ref "J11") (pin "9") (pinfunction "9_9") (pintype "passive"))
      (node (ref "R18") (pin "P$1") (pinfunction "1_P$1") (pintype "passive"))
      (node (ref "U4") (pin "67") (pinfunction "RES#_67") (pintype "bidirectional"))
    )
    (net (code "141") (name "REXT") (class "Default")
      (node (ref "C47") (pin "P$1") (pinfunction "1_P$1") (pintype "passive"))
      (node (ref "R25") (pin "P$2") (pinfunction "2_P$2") (pintype "passive"))
      (node (ref "U3") (pin "9") (pinfunction "REXT_9") (pintype "input"))
    )
    (net (code "142") (name "RST") (class "Default")
      (node (ref "U$2") (pin "P20") (pinfunction "RST_P20") (pintype "bidirectional"))
      (node (ref "U4") (pin "121") (pinfunction "P6_1_121") (pintype "bidirectional"))
    )
    (net (code "143") (name "RXD0") (class "Default")
      (node (ref "R31") (pin "P$2") (pinfunction "2_P$2") (pintype "passive"))
      (node (ref "U3") (pin "13") (pinfunction "RXD0_13") (pintype "bidirectional"))
    )
    (net (code "144") (name "RXD1") (class "Default")
      (node (ref "R30") (pin "P$2") (pinfunction "2_P$2") (pintype "passive"))
      (node (ref "U3") (pin "12") (pinfunction "RXD1_12") (pintype "bidirectional"))
    )
    (net (code "145") (name "RXER") (class "Default")
      (node (ref "R32") (pin "P$2") (pinfunction "2_P$2") (pintype "passive"))
      (node (ref "U3") (pin "17") (pinfunction "RXER_17") (pintype "bidirectional"))
    )
    (net (code "146") (name "RXM") (class "Default")
      (node (ref "J4") (pin "6") (pinfunction "RD-_6") (pintype "bidirectional"))
      (node (ref "U3") (pin "3") (pinfunction "RXM_3") (pintype "bidirectional"))
    )
    (net (code "147") (name "RXP") (class "Default")
      (node (ref "J4") (pin "3") (pinfunction "RD+_3") (pintype "bidirectional"))
      (node (ref "U3") (pin "4") (pinfunction "RXP_4") (pintype "bidirectional"))
    )
    (net (code "148") (name "SPI_0_CS_0") (class "Default")
      (node (ref "U$2") (pin "P16") (pinfunction "CS_P16") (pintype "bidirectional"))
      (node (ref "U4") (pin "129") (pinfunction "P1_3_129") (pintype "bidirectional"))
    )
    (net (code "149") (name "SPI_0_MISO") (class "Default")
      (node (ref "U$2") (pin "P18") (pinfunction "SDO_P18") (pintype "bidirectional"))
      (node (ref "U4") (pin "132") (pinfunction "P1_0_132") (pintype "bidirectional"))
    )
    (net (code "150") (name "SPI_0_MOSI") (class "Default")
      (node (ref "U$2") (pin "P15") (pinfunction "SDI_P15") (pintype "bidirectional"))
      (node (ref "U4") (pin "131") (pinfunction "P1_1_131") (pintype "bidirectional"))
    )
    (net (code "151") (name "SPI_0_SCLK") (class "Default")
      (node (ref "U$2") (pin "P17") (pinfunction "SCLK_P17") (pintype "bidirectional"))
      (node (ref "U4") (pin "130") (pinfunction "P1_2_130") (pintype "bidirectional"))
    )
    (net (code "152") (name "SPI_1_CS_0") (class "Default")
      (node (ref "J12") (pin "P$24") (pinfunction "CE0_P$24") (pintype "output"))
      (node (ref "U4") (pin "55") (pinfunction "P3_13_55") (pintype "bidirectional"))
    )
    (net (code "153") (name "SPI_1_CS_1") (class "Default")
      (node (ref "J12") (pin "P$26") (pinfunction "CE1_P$26") (pintype "output"))
      (node (ref "U4") (pin "74") (pinfunction "P3_12_74") (pintype "bidirectional"))
    )
    (net (code "154") (name "SPI_1_MISO") (class "Default")
      (node (ref "J12") (pin "P$21") (pinfunction "MISO_P$21") (pintype "input"))
      (node (ref "U4") (pin "54") (pinfunction "P2_2_54") (pintype "bidirectional"))
    )
    (net (code "155") (name "SPI_1_MOSI") (class "Default")
      (node (ref "J12") (pin "P$19") (pinfunction "MOSI_P$19") (pintype "output"))
      (node (ref "U4") (pin "53") (pinfunction "P2_3_53") (pintype "bidirectional"))
    )
    (net (code "156") (name "SPI_1_SCLK") (class "Default")
      (node (ref "J12") (pin "P$23") (pinfunction "SCLK_P$23") (pintype "output"))
      (node (ref "U4") (pin "52") (pinfunction "P2_4_52") (pintype "bidirectional"))
    )
    (net (code "157") (name "TCK") (class "Default")
      (node (ref "J11") (pin "7") (pinfunction "7_7") (pintype "passive"))
      (node (ref "U4") (pin "88") (pinfunction "P3_0_88") (pintype "bidirectional"))
    )
    (net (code "158") (name "TDI") (class "Default")
      (node (ref "J11") (pin "1") (pinfunction "1_1") (pintype "passive"))
      (node (ref "U4") (pin "91") (pinfunction "P1_10_91") (pintype "bidirectional"))
    )
    (net (code "159") (name "TDO") (class "Default")
      (node (ref "J11") (pin "3") (pinfunction "3_3") (pintype "passive"))
      (node (ref "U4") (pin "90") (pinfunction "P1_9_90") (pintype "bidirectional"))
    )
    (net (code "160") (name "TMS") (class "Default")
      (node (ref "J11") (pin "5") (pinfunction "5_5") (pintype "passive"))
      (node (ref "U4") (pin "89") (pinfunction "P1_8_89") (pintype "bidirectional"))
    )
    (net (code "161") (name "TXM") (class "Default")
      (node (ref "J4") (pin "2") (pinfunction "TD-_2") (pintype "bidirectional"))
      (node (ref "U3") (pin "5") (pinfunction "TXM_5") (pintype "bidirectional"))
    )
    (net (code "162") (name "TXP") (class "Default")
      (node (ref "J4") (pin "1") (pinfunction "TD+_1") (pintype "bidirectional"))
      (node (ref "U3") (pin "6") (pinfunction "TXP_6") (pintype "bidirectional"))
    )
    (net (code "163") (name "UC") (class "Default")
      (node (ref "C20") (pin "P$1") (pinfunction "P$1_P$1") (pintype "bidirectional"))
      (node (ref "U$2") (pin "P22") (pinfunction "VAC_240_P22") (pintype "bidirectional"))
      (node (ref "U$7") (pin "P$1") (pinfunction "P$1_P$1") (pintype "bidirectional"))
      (node (ref "U5") (pin "P$5") (pinfunction "AC_L_P$5") (pintype "bidirectional"))
    )
    (net (code "164") (name "USBHS_FAULT") (class "Default")
      (node (ref "R12") (pin "P$1") (pinfunction "1_P$1") (pintype "passive"))
      (node (ref "U2") (pin "3") (pinfunction "FLG_3") (pintype "input"))
      (node (ref "U4") (pin "78") (pinfunction "P3_8_78") (pintype "bidirectional"))
    )
    (net (code "165") (name "USBHS_N") (class "Default")
      (node (ref "J3") (pin "D-") (pinfunction "D-_D-") (pintype "bidirectional"))
      (node (ref "U4") (pin "31") (pinfunction "USBHS_DM_31") (pintype "bidirectional"))
    )
    (net (code "166") (name "USBHS_P") (class "Default")
      (node (ref "J3") (pin "D+") (pinfunction "D+_D+") (pintype "bidirectional"))
      (node (ref "U4") (pin "32") (pinfunction "USBHS_DP_32") (pintype "bidirectional"))
    )
    (net (code "167") (name "USBHS_VBUS") (class "Default")
      (node (ref "C11") (pin "P$1") (pinfunction "1_P$1") (pintype "passive"))
      (node (ref "C15") (pin "1") (pinfunction "1_1") (pintype "passive"))
      (node (ref "J3") (pin "VBUS") (pinfunction "VBUS_VBUS") (pintype "power_in"))
      (node (ref "U2") (pin "5") (pinfunction "OUT_5") (pintype "input"))
      (node (ref "U4") (pin "17") (pinfunction "PB_1_17") (pintype "bidirectional"))
    )
    (net (code "168") (name "USBHS_VBUSEN") (class "Default")
      (node (ref "R1") (pin "P$1") (pinfunction "1_P$1") (pintype "passive"))
      (node (ref "U2") (pin "1") (pinfunction "EN_1") (pintype "input"))
    )
    (net (code "169") (name "USB_N") (class "Default")
      (node (ref "R5") (pin "P$1") (pinfunction "1_P$1") (pintype "passive"))
      (node (ref "U4") (pin "46") (pinfunction "USB_DM_46") (pintype "bidirectional"))
    )
    (net (code "170") (name "USB_P") (class "Default")
      (node (ref "R6") (pin "P$1") (pinfunction "1_P$1") (pintype "passive"))
      (node (ref "U4") (pin "47") (pinfunction "USB_DP_47") (pintype "bidirectional"))
    )
    (net (code "171") (name "USB_VBUS") (class "Default")
      (node (ref "C4") (pin "P$1") (pinfunction "1_P$1") (pintype "passive"))
      (node (ref "J2") (pin "P$1") (pinfunction "VBUS_P$1") (pintype "bidirectional"))
      (node (ref "R10") (pin "P$2") (pinfunction "2_P$2") (pintype "passive"))
      (node (ref "U1") (pin "1") (pinfunction "VBUS1_1") (pintype "bidirectional"))
    )
    (net (code "172") (name "USB_VBUS_B") (class "Default")
      (node (ref "R7") (pin "P$1") (pinfunction "1_P$1") (pintype "passive"))
      (node (ref "U4") (pin "44") (pinfunction "P4_7_44") (pintype "bidirectional"))
    )
    (net (code "173") (name "VCC") (class "Default")
      (node (ref "C21") (pin "P$1") (pinfunction "1_P$1") (pintype "passive"))
      (node (ref "C22") (pin "P$1") (pinfunction "1_P$1") (pintype "passive"))
      (node (ref "C23") (pin "1") (pinfunction "1_1") (pintype "passive"))
      (node (ref "C24") (pin "P$1") (pinfunction "1_P$1") (pintype "passive"))
      (node (ref "IC3") (pin "1") (pinfunction "IN_1") (pintype "input"))
      (node (ref "IC4") (pin "1") (pinfunction "IN_1") (pintype "input"))
      (node (ref "U$8") (pin "P+") (pinfunction "+_P+") (pintype "passive"))
      (node (ref "U5") (pin "P$2") (pinfunction "VOUT+_P$2") (pintype "bidirectional"))
    )
    (net (code "174") (name "VCL_F(FLASH)") (class "Default")
      (node (ref "C36") (pin "P$2") (pinfunction "2_P$2") (pintype "passive"))
      (node (ref "U4") (pin "112") (pinfunction "VCL_F(FLASH)_112") (pintype "bidirectional"))
    )
    (net (code "175") (name "VDD") (class "Default")
      (node (ref "C1") (pin "P$2") (pinfunction "2_P$2") (pintype "passive"))
      (node (ref "C10") (pin "P$2") (pinfunction "2_P$2") (pintype "passive"))
      (node (ref "C13") (pin "P$2") (pinfunction "2_P$2") (pintype "passive"))
      (node (ref "C14") (pin "P$2") (pinfunction "2_P$2") (pintype "passive"))
      (node (ref "C19") (pin "P$1") (pinfunction "1_P$1") (pintype "passive"))
      (node (ref "C2") (pin "P$2") (pinfunction "2_P$2") (pintype "passive"))
      (node (ref "C25") (pin "P$1") (pinfunction "1_P$1") (pintype "passive"))
      (node (ref "C26") (pin "1") (pinfunction "1_1") (pintype "passive"))
      (node (ref "C29") (pin "P$1") (pinfunction "1_P$1") (pintype "passive"))
      (node (ref "C30") (pin "P$2") (pinfunction "2_P$2") (pintype "passive"))
      (node (ref "C32") (pin "P$1") (pinfunction "1_P$1") (pintype "passive"))
      (node (ref "C48") (pin "1") (pinfunction "1_1") (pintype "passive"))
      (node (ref "C49") (pin "P$1") (pinfunction "1_P$1") (pintype "passive"))
      (node (ref "C54") (pin "P$2") (pinfunction "2_P$2") (pintype "passive"))
      (node (ref "C55") (pin "P$2") (pinfunction "2_P$2") (pintype "passive"))
      (node (ref "C56") (pin "P$2") (pinfunction "2_P$2") (pintype "passive"))
      (node (ref "C58") (pin "P$1") (pinfunction "1_P$1") (pintype "passive"))
      (node (ref "C59") (pin "P$1") (pinfunction "1_P$1") (pintype "passive"))
      (node (ref "C60") (pin "P$1") (pinfunction "1_P$1") (pintype "passive"))
      (node (ref "C61") (pin "P$2") (pinfunction "2_P$2") (pintype "passive"))
      (node (ref "C62") (pin "P$1") (pinfunction "1_P$1") (pintype "passive"))
      (node (ref "C63") (pin "P$1") (pinfunction "1_P$1") (pintype "passive"))
      (node (ref "FB2/2") (pin "1") (pinfunction "P$1_1") (pintype "bidirectional"))
      (node (ref "IC4") (pin "3") (pinfunction "OUT_3") (pintype "output"))
      (node (ref "J1") (pin "P$20") (pinfunction "P$20_P$20") (pintype "bidirectional"))
      (node (ref "J11") (pin "2") (pinfunction "2_2") (pintype "passive"))
      (node (ref "J11") (pin "4") (pinfunction "4_4") (pintype "passive"))
      (node (ref "J12") (pin "P$1") (pinfunction "3.3V_P$1") (pintype "power_in"))
      (node (ref "J12") (pin "P$17") (pinfunction "3.3V_P$17") (pintype "power_in"))
      (node (ref "R18") (pin "P$2") (pinfunction "2_P$2") (pintype "passive"))
      (node (ref "R23") (pin "P$2") (pinfunction "2_P$2") (pintype "passive"))
      (node (ref "R24") (pin "P$2") (pinfunction "2_P$2") (pintype "passive"))
      (node (ref "R26") (pin "P$2") (pinfunction "2_P$2") (pintype "passive"))
      (node (ref "R27") (pin "P$2") (pinfunction "2_P$2") (pintype "passive"))
      (node (ref "R28") (pin "P$2") (pinfunction "2_P$2") (pintype "passive"))
      (node (ref "R29") (pin "P$2") (pinfunction "2_P$2") (pintype "passive"))
      (node (ref "R8") (pin "P$1") (pinfunction "1_P$1") (pintype "passive"))
      (node (ref "U$2") (pin "P19") (pinfunction "VDD_P19") (pintype "bidirectional"))
      (node (ref "U3") (pin "14") (pinfunction "VDDIO_14") (pintype "power_in"))
      (node (ref "U4") (pin "110") (pinfunction "VCC(IO)5_110") (pintype "bidirectional"))
      (node (ref "U4") (pin "123") (pinfunction "VCC(IO)6_123") (pintype "bidirectional"))
      (node (ref "U4") (pin "138") (pinfunction "VCC(IO)7_138") (pintype "bidirectional"))
      (node (ref "U4") (pin "149") (pinfunction "VCC(IO)8_149") (pintype "bidirectional"))
      (node (ref "U4") (pin "154") (pinfunction "VREFH_154") (pintype "bidirectional"))
      (node (ref "U4") (pin "155") (pinfunction "AVCC0_155") (pintype "bidirectional"))
      (node (ref "U4") (pin "158") (pinfunction "VREFH0_158") (pintype "bidirectional"))
      (node (ref "U4") (pin "171") (pinfunction "VCC(IO)9_171") (pintype "bidirectional"))
      (node (ref "U4") (pin "25") (pinfunction "VCC1_25") (pintype "bidirectional"))
      (node (ref "U4") (pin "26") (pinfunction "AVCC_SUBHS_26") (pintype "bidirectional"))
      (node (ref "U4") (pin "34") (pinfunction "VCC_USBHS_34") (pintype "bidirectional"))
      (node (ref "U4") (pin "48") (pinfunction "VCC_USB_48") (pintype "bidirectional"))
      (node (ref "U4") (pin "61") (pinfunction "VCC(IO)2_61") (pintype "bidirectional"))
      (node (ref "U4") (pin "84") (pinfunction "VCC(IO)3_84") (pintype "bidirectional"))
      (node (ref "U4") (pin "97") (pinfunction "VCC(IO)4_97") (pintype "bidirectional"))
      (node (ref "U6") (pin "7") (pinfunction "+VS_7") (pintype "power_in"))
      (node (ref "U7") (pin "7") (pinfunction "+VS_7") (pintype "power_in"))
    )
    (net (code "176") (name "VDD5") (class "Default")
      (node (ref "C27") (pin "P$1") (pinfunction "1_P$1") (pintype "passive"))
      (node (ref "C28") (pin "1") (pinfunction "1_1") (pintype "passive"))
      (node (ref "C5") (pin "P$1") (pinfunction "1_P$1") (pintype "passive"))
      (node (ref "C6") (pin "P$2") (pinfunction "2_P$2") (pintype "passive"))
      (node (ref "C65") (pin "P$1") (pinfunction "1_P$1") (pintype "passive"))
      (node (ref "C8") (pin "P$1") (pinfunction "1_P$1") (pintype "passive"))
      (node (ref "IC3") (pin "3") (pinfunction "OUT_3") (pintype "output"))
      (node (ref "J12") (pin "P$2") (pinfunction "5V_P$2") (pintype "power_in"))
      (node (ref "J12") (pin "P$4") (pinfunction "5V_P$4") (pintype "power_in"))
      (node (ref "R1") (pin "P$2") (pinfunction "2_P$2") (pintype "passive"))
      (node (ref "R12") (pin "P$2") (pinfunction "2_P$2") (pintype "passive"))
      (node (ref "R34") (pin "P$2") (pinfunction "2_P$2") (pintype "passive"))
      (node (ref "R7") (pin "P$2") (pinfunction "2_P$2") (pintype "passive"))
      (node (ref "R9") (pin "P$1") (pinfunction "1_P$1") (pintype "passive"))
      (node (ref "U1") (pin "16") (pinfunction "VBUS2_16") (pintype "bidirectional"))
      (node (ref "U2") (pin "4") (pinfunction "VIN_4") (pintype "input"))
    )
    (net (code "177") (name "VDD_1.2") (class "Default")
      (node (ref "C45") (pin "P$1") (pinfunction "1_P$1") (pintype "passive"))
      (node (ref "C46") (pin "P$1") (pinfunction "1_P$1") (pintype "passive"))
      (node (ref "U3") (pin "1") (pinfunction "VDD_1.2_1") (pintype "power_in"))
    )
    (net (code "178") (name "WARNOUT") (class "Default")
      (node (ref "U$2") (pin "P9") (pinfunction "WARNOUT_P9") (pintype "bidirectional"))
      (node (ref "U4") (pin "128") (pinfunction "P1_4_128") (pintype "bidirectional"))
    )
    (net (code "179") (name "XCIN") (class "Default")
      (node (ref "C50") (pin "P$1") (pinfunction "1_P$1") (pintype "passive"))
      (node (ref "U4") (pin "20") (pinfunction "XCIN_20") (pintype "bidirectional"))
      (node (ref "X3") (pin "P$1") (pinfunction "P$1_P$1") (pintype "bidirectional"))
    )
    (net (code "180") (name "XCOUT") (class "Default")
      (node (ref "C51") (pin "P$1") (pinfunction "1_P$1") (pintype "passive"))
      (node (ref "U4") (pin "21") (pinfunction "XCOUT_21") (pintype "bidirectional"))
      (node (ref "X3") (pin "P$2") (pinfunction "P$2_P$2") (pintype "bidirectional"))
    )
    (net (code "181") (name "XII") (class "Default")
      (node (ref "C42") (pin "P$1") (pinfunction "1_P$1") (pintype "passive"))
      (node (ref "U$3") (pin "1") (pinfunction "1_1") (pintype "bidirectional"))
      (node (ref "U3") (pin "8") (pinfunction "XI_8") (pintype "input"))
    )
    (net (code "182") (name "XOO") (class "Default")
      (node (ref "C41") (pin "P$1") (pinfunction "1_P$1") (pintype "passive"))
      (node (ref "U$3") (pin "3") (pinfunction "3_3") (pintype "bidirectional"))
      (node (ref "U3") (pin "7") (pinfunction "XO_7") (pintype "output"))
    )
    (net (code "183") (name "XTAL1") (class "Default")
      (node (ref "C52") (pin "P$1") (pinfunction "1_P$1") (pintype "passive"))
      (node (ref "U4") (pin "23") (pinfunction "P2_13/XTAL_23") (pintype "bidirectional"))
      (node (ref "X4") (pin "1") (pinfunction "1_1") (pintype "bidirectional"))
    )
    (net (code "184") (name "XTAL2") (class "Default")
      (node (ref "C53") (pin "P$1") (pinfunction "1_P$1") (pintype "passive"))
      (node (ref "U4") (pin "24") (pinfunction "P2_12/EXTAL_24") (pintype "bidirectional"))
      (node (ref "X4") (pin "3") (pinfunction "3_3") (pintype "bidirectional"))
    )
    (net (code "185") (name "ZX0") (class "Default")
      (node (ref "U$2") (pin "P2") (pinfunction "ZX0_P2") (pintype "bidirectional"))
      (node (ref "U4") (pin "135") (pinfunction "P8_2_135") (pintype "bidirectional"))
    )
    (net (code "186") (name "ZX1") (class "Default")
      (node (ref "U$2") (pin "P3") (pinfunction "ZX1_P3") (pintype "bidirectional"))
      (node (ref "U4") (pin "134") (pinfunction "P8_1_134") (pintype "bidirectional"))
    )
    (net (code "187") (name "ZX2") (class "Default")
      (node (ref "U$2") (pin "P4") (pinfunction "ZX2_P4") (pintype "bidirectional"))
      (node (ref "U4") (pin "133") (pinfunction "P8_0_133") (pintype "bidirectional"))
    )
    (net (code "188") (name "unconnected-(J2-ID-PadP$4)") (class "Default")
      (node (ref "J2") (pin "P$4") (pinfunction "ID_P$4") (pintype "bidirectional"))
    )
    (net (code "189") (name "unconnected-(U4-VBAT-Pad18)") (class "Default")
      (node (ref "U4") (pin "18") (pinfunction "VBAT_18") (pintype "bidirectional"))
    )
    (net (code "190") (name "unconnected-(U5-NC1-PadP$1)") (class "Default")
      (node (ref "U5") (pin "P$1") (pinfunction "NC1_P$1") (pintype "bidirectional"))
    )
    (net (code "191") (name "unconnected-(U5-NC2-PadP$4)") (class "Default")
      (node (ref "U5") (pin "P$4") (pinfunction "NC2_P$4") (pintype "bidirectional"))
    )
    (net (code "192") (name "unconnected-(U5-NC3-PadP$7)") (class "Default")
      (node (ref "U5") (pin "P$7") (pinfunction "NC3_P$7") (pintype "bidirectional"))
    )
    (net (code "193") (name "unconnected-(U6-NC-Pad4)") (class "Default")
      (node (ref "U6") (pin "4") (pinfunction "NC_4") (pintype "no_connect"))
    )
    (net (code "194") (name "unconnected-(U7-NC-Pad4)") (class "Default")
      (node (ref "U7") (pin "4") (pinfunction "NC_4") (pintype "no_connect"))
    )
  )
)
